# Sheet1.net
KiCad netlist of a schematic drawn in Altium Designer
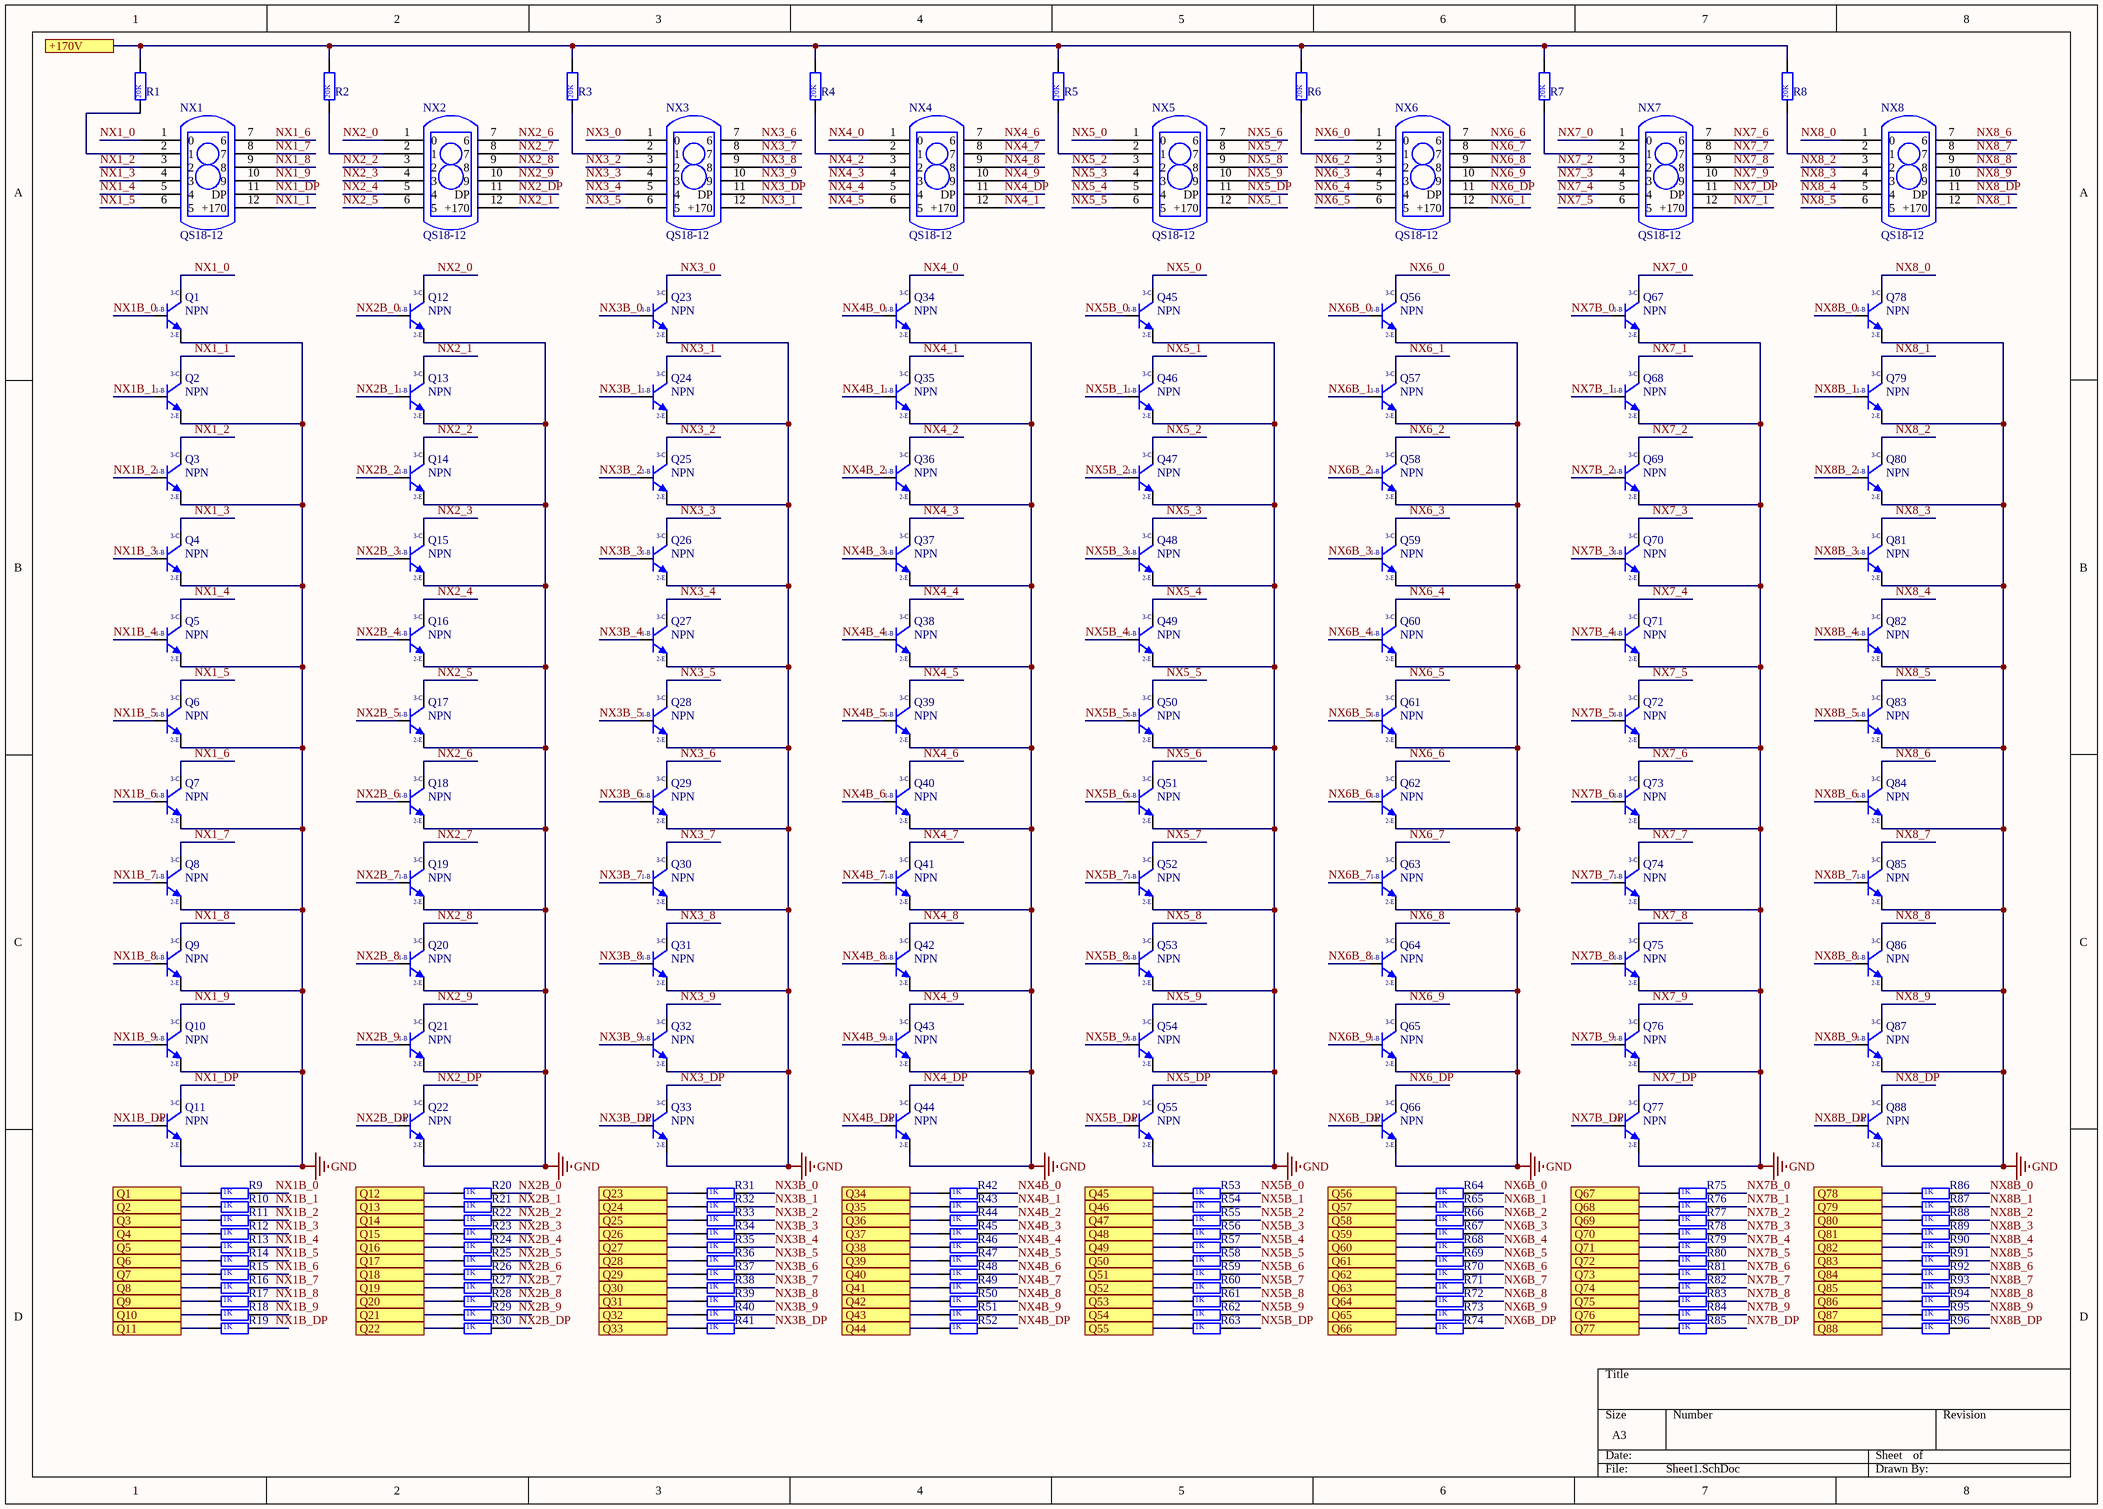
[diagram p0: Sheet1.SchDoc]

(export (version "E")
  (design (tool "Eeschema 10.0.6"))
  (components
    (comp (ref "NX1")
      (value "QS18-12")
      (footprint "PCBComponent_1")
      (libsource (lib "Nixie") (part "QS18-12"))
    )
    (comp (ref "NX2")
      (value "QS18-12")
      (footprint "PCBComponent_1")
      (libsource (lib "Nixie") (part "QS18-12"))
    )
    (comp (ref "NX3")
      (value "QS18-12")
      (footprint "PCBComponent_1")
      (libsource (lib "Nixie") (part "QS18-12"))
    )
    (comp (ref "NX4")
      (value "QS18-12")
      (footprint "PCBComponent_1")
      (libsource (lib "Nixie") (part "QS18-12"))
    )
    (comp (ref "NX5")
      (value "QS18-12")
      (footprint "PCBComponent_1")
      (libsource (lib "Nixie") (part "QS18-12"))
    )
    (comp (ref "NX6")
      (value "QS18-12")
      (footprint "PCBComponent_1")
      (libsource (lib "Nixie") (part "QS18-12"))
    )
    (comp (ref "NX7")
      (value "QS18-12")
      (footprint "PCBComponent_1")
      (libsource (lib "Nixie") (part "QS18-12"))
    )
    (comp (ref "NX8")
      (value "QS18-12")
      (footprint "PCBComponent_1")
      (libsource (lib "Nixie") (part "QS18-12"))
    )
    (comp (ref "Q1") (value "NPN") (footprint "SOT-23") (libsource (lib "吴原理图库") (part "NPN-S8050-SOT-23")))
    (comp (ref "Q2") (value "NPN") (footprint "SOT-23") (libsource (lib "吴原理图库") (part "NPN-S8050-SOT-23")))
    (comp (ref "Q3") (value "NPN") (footprint "SOT-23") (libsource (lib "吴原理图库") (part "NPN-S8050-SOT-23")))
    (comp (ref "Q4") (value "NPN") (footprint "SOT-23") (libsource (lib "吴原理图库") (part "NPN-S8050-SOT-23")))
    (comp (ref "Q5") (value "NPN") (footprint "SOT-23") (libsource (lib "吴原理图库") (part "NPN-S8050-SOT-23")))
    (comp (ref "Q6") (value "NPN") (footprint "SOT-23") (libsource (lib "吴原理图库") (part "NPN-S8050-SOT-23")))
    (comp (ref "Q7") (value "NPN") (footprint "SOT-23") (libsource (lib "吴原理图库") (part "NPN-S8050-SOT-23")))
    (comp (ref "Q8") (value "NPN") (footprint "SOT-23") (libsource (lib "吴原理图库") (part "NPN-S8050-SOT-23")))
    (comp (ref "Q9") (value "NPN") (footprint "SOT-23") (libsource (lib "吴原理图库") (part "NPN-S8050-SOT-23")))
    (comp (ref "Q10") (value "NPN") (footprint "SOT-23") (libsource (lib "吴原理图库") (part "NPN-S8050-SOT-23")))
    (comp (ref "Q11") (value "NPN") (footprint "SOT-23") (libsource (lib "吴原理图库") (part "NPN-S8050-SOT-23")))
    (comp (ref "Q12") (value "NPN") (footprint "SOT-23") (libsource (lib "吴原理图库") (part "NPN-S8050-SOT-23")))
    (comp (ref "Q13") (value "NPN") (footprint "SOT-23") (libsource (lib "吴原理图库") (part "NPN-S8050-SOT-23")))
    (comp (ref "Q14") (value "NPN") (footprint "SOT-23") (libsource (lib "吴原理图库") (part "NPN-S8050-SOT-23")))
    (comp (ref "Q15") (value "NPN") (footprint "SOT-23") (libsource (lib "吴原理图库") (part "NPN-S8050-SOT-23")))
    (comp (ref "Q16") (value "NPN") (footprint "SOT-23") (libsource (lib "吴原理图库") (part "NPN-S8050-SOT-23")))
    (comp (ref "Q17") (value "NPN") (footprint "SOT-23") (libsource (lib "吴原理图库") (part "NPN-S8050-SOT-23")))
    (comp (ref "Q18") (value "NPN") (footprint "SOT-23") (libsource (lib "吴原理图库") (part "NPN-S8050-SOT-23")))
    (comp (ref "Q19") (value "NPN") (footprint "SOT-23") (libsource (lib "吴原理图库") (part "NPN-S8050-SOT-23")))
    (comp (ref "Q20") (value "NPN") (footprint "SOT-23") (libsource (lib "吴原理图库") (part "NPN-S8050-SOT-23")))
    (comp (ref "Q21") (value "NPN") (footprint "SOT-23") (libsource (lib "吴原理图库") (part "NPN-S8050-SOT-23")))
    (comp (ref "Q22") (value "NPN") (footprint "SOT-23") (libsource (lib "吴原理图库") (part "NPN-S8050-SOT-23")))
    (comp (ref "Q23") (value "NPN") (footprint "SOT-23") (libsource (lib "吴原理图库") (part "NPN-S8050-SOT-23")))
    (comp (ref "Q24") (value "NPN") (footprint "SOT-23") (libsource (lib "吴原理图库") (part "NPN-S8050-SOT-23")))
    (comp (ref "Q25") (value "NPN") (footprint "SOT-23") (libsource (lib "吴原理图库") (part "NPN-S8050-SOT-23")))
    (comp (ref "Q26") (value "NPN") (footprint "SOT-23") (libsource (lib "吴原理图库") (part "NPN-S8050-SOT-23")))
    (comp (ref "Q27") (value "NPN") (footprint "SOT-23") (libsource (lib "吴原理图库") (part "NPN-S8050-SOT-23")))
    (comp (ref "Q28") (value "NPN") (footprint "SOT-23") (libsource (lib "吴原理图库") (part "NPN-S8050-SOT-23")))
    (comp (ref "Q29") (value "NPN") (footprint "SOT-23") (libsource (lib "吴原理图库") (part "NPN-S8050-SOT-23")))
    (comp (ref "Q30") (value "NPN") (footprint "SOT-23") (libsource (lib "吴原理图库") (part "NPN-S8050-SOT-23")))
    (comp (ref "Q31") (value "NPN") (footprint "SOT-23") (libsource (lib "吴原理图库") (part "NPN-S8050-SOT-23")))
    (comp (ref "Q32") (value "NPN") (footprint "SOT-23") (libsource (lib "吴原理图库") (part "NPN-S8050-SOT-23")))
    (comp (ref "Q33") (value "NPN") (footprint "SOT-23") (libsource (lib "吴原理图库") (part "NPN-S8050-SOT-23")))
    (comp (ref "Q34") (value "NPN") (footprint "SOT-23") (libsource (lib "吴原理图库") (part "NPN-S8050-SOT-23")))
    (comp (ref "Q35") (value "NPN") (footprint "SOT-23") (libsource (lib "吴原理图库") (part "NPN-S8050-SOT-23")))
    (comp (ref "Q36") (value "NPN") (footprint "SOT-23") (libsource (lib "吴原理图库") (part "NPN-S8050-SOT-23")))
    (comp (ref "Q37") (value "NPN") (footprint "SOT-23") (libsource (lib "吴原理图库") (part "NPN-S8050-SOT-23")))
    (comp (ref "Q38") (value "NPN") (footprint "SOT-23") (libsource (lib "吴原理图库") (part "NPN-S8050-SOT-23")))
    (comp (ref "Q39") (value "NPN") (footprint "SOT-23") (libsource (lib "吴原理图库") (part "NPN-S8050-SOT-23")))
    (comp (ref "Q40") (value "NPN") (footprint "SOT-23") (libsource (lib "吴原理图库") (part "NPN-S8050-SOT-23")))
    (comp (ref "Q41") (value "NPN") (footprint "SOT-23") (libsource (lib "吴原理图库") (part "NPN-S8050-SOT-23")))
    (comp (ref "Q42") (value "NPN") (footprint "SOT-23") (libsource (lib "吴原理图库") (part "NPN-S8050-SOT-23")))
    (comp (ref "Q43") (value "NPN") (footprint "SOT-23") (libsource (lib "吴原理图库") (part "NPN-S8050-SOT-23")))
    (comp (ref "Q44") (value "NPN") (footprint "SOT-23") (libsource (lib "吴原理图库") (part "NPN-S8050-SOT-23")))
    (comp (ref "Q45") (value "NPN") (footprint "SOT-23") (libsource (lib "吴原理图库") (part "NPN-S8050-SOT-23")))
    (comp (ref "Q46") (value "NPN") (footprint "SOT-23") (libsource (lib "吴原理图库") (part "NPN-S8050-SOT-23")))
    (comp (ref "Q47") (value "NPN") (footprint "SOT-23") (libsource (lib "吴原理图库") (part "NPN-S8050-SOT-23")))
    (comp (ref "Q48") (value "NPN") (footprint "SOT-23") (libsource (lib "吴原理图库") (part "NPN-S8050-SOT-23")))
    (comp (ref "Q49") (value "NPN") (footprint "SOT-23") (libsource (lib "吴原理图库") (part "NPN-S8050-SOT-23")))
    (comp (ref "Q50") (value "NPN") (footprint "SOT-23") (libsource (lib "吴原理图库") (part "NPN-S8050-SOT-23")))
    (comp (ref "Q51") (value "NPN") (footprint "SOT-23") (libsource (lib "吴原理图库") (part "NPN-S8050-SOT-23")))
    (comp (ref "Q52") (value "NPN") (footprint "SOT-23") (libsource (lib "吴原理图库") (part "NPN-S8050-SOT-23")))
    (comp (ref "Q53") (value "NPN") (footprint "SOT-23") (libsource (lib "吴原理图库") (part "NPN-S8050-SOT-23")))
    (comp (ref "Q54") (value "NPN") (footprint "SOT-23") (libsource (lib "吴原理图库") (part "NPN-S8050-SOT-23")))
    (comp (ref "Q55") (value "NPN") (footprint "SOT-23") (libsource (lib "吴原理图库") (part "NPN-S8050-SOT-23")))
    (comp (ref "Q56") (value "NPN") (footprint "SOT-23") (libsource (lib "吴原理图库") (part "NPN-S8050-SOT-23")))
    (comp (ref "Q57") (value "NPN") (footprint "SOT-23") (libsource (lib "吴原理图库") (part "NPN-S8050-SOT-23")))
    (comp (ref "Q58") (value "NPN") (footprint "SOT-23") (libsource (lib "吴原理图库") (part "NPN-S8050-SOT-23")))
    (comp (ref "Q59") (value "NPN") (footprint "SOT-23") (libsource (lib "吴原理图库") (part "NPN-S8050-SOT-23")))
    (comp (ref "Q60") (value "NPN") (footprint "SOT-23") (libsource (lib "吴原理图库") (part "NPN-S8050-SOT-23")))
    (comp (ref "Q61") (value "NPN") (footprint "SOT-23") (libsource (lib "吴原理图库") (part "NPN-S8050-SOT-23")))
    (comp (ref "Q62") (value "NPN") (footprint "SOT-23") (libsource (lib "吴原理图库") (part "NPN-S8050-SOT-23")))
    (comp (ref "Q63") (value "NPN") (footprint "SOT-23") (libsource (lib "吴原理图库") (part "NPN-S8050-SOT-23")))
    (comp (ref "Q64") (value "NPN") (footprint "SOT-23") (libsource (lib "吴原理图库") (part "NPN-S8050-SOT-23")))
    (comp (ref "Q65") (value "NPN") (footprint "SOT-23") (libsource (lib "吴原理图库") (part "NPN-S8050-SOT-23")))
    (comp (ref "Q66") (value "NPN") (footprint "SOT-23") (libsource (lib "吴原理图库") (part "NPN-S8050-SOT-23")))
    (comp (ref "Q67") (value "NPN") (footprint "SOT-23") (libsource (lib "吴原理图库") (part "NPN-S8050-SOT-23")))
    (comp (ref "Q68") (value "NPN") (footprint "SOT-23") (libsource (lib "吴原理图库") (part "NPN-S8050-SOT-23")))
    (comp (ref "Q69") (value "NPN") (footprint "SOT-23") (libsource (lib "吴原理图库") (part "NPN-S8050-SOT-23")))
    (comp (ref "Q70") (value "NPN") (footprint "SOT-23") (libsource (lib "吴原理图库") (part "NPN-S8050-SOT-23")))
    (comp (ref "Q71") (value "NPN") (footprint "SOT-23") (libsource (lib "吴原理图库") (part "NPN-S8050-SOT-23")))
    (comp (ref "Q72") (value "NPN") (footprint "SOT-23") (libsource (lib "吴原理图库") (part "NPN-S8050-SOT-23")))
    (comp (ref "Q73") (value "NPN") (footprint "SOT-23") (libsource (lib "吴原理图库") (part "NPN-S8050-SOT-23")))
    (comp (ref "Q74") (value "NPN") (footprint "SOT-23") (libsource (lib "吴原理图库") (part "NPN-S8050-SOT-23")))
    (comp (ref "Q75") (value "NPN") (footprint "SOT-23") (libsource (lib "吴原理图库") (part "NPN-S8050-SOT-23")))
    (comp (ref "Q76") (value "NPN") (footprint "SOT-23") (libsource (lib "吴原理图库") (part "NPN-S8050-SOT-23")))
    (comp (ref "Q77") (value "NPN") (footprint "SOT-23") (libsource (lib "吴原理图库") (part "NPN-S8050-SOT-23")))
    (comp (ref "Q78") (value "NPN") (footprint "SOT-23") (libsource (lib "吴原理图库") (part "NPN-S8050-SOT-23")))
    (comp (ref "Q79") (value "NPN") (footprint "SOT-23") (libsource (lib "吴原理图库") (part "NPN-S8050-SOT-23")))
    (comp (ref "Q80") (value "NPN") (footprint "SOT-23") (libsource (lib "吴原理图库") (part "NPN-S8050-SOT-23")))
    (comp (ref "Q81") (value "NPN") (footprint "SOT-23") (libsource (lib "吴原理图库") (part "NPN-S8050-SOT-23")))
    (comp (ref "Q82") (value "NPN") (footprint "SOT-23") (libsource (lib "吴原理图库") (part "NPN-S8050-SOT-23")))
    (comp (ref "Q83") (value "NPN") (footprint "SOT-23") (libsource (lib "吴原理图库") (part "NPN-S8050-SOT-23")))
    (comp (ref "Q84") (value "NPN") (footprint "SOT-23") (libsource (lib "吴原理图库") (part "NPN-S8050-SOT-23")))
    (comp (ref "Q85") (value "NPN") (footprint "SOT-23") (libsource (lib "吴原理图库") (part "NPN-S8050-SOT-23")))
    (comp (ref "Q86") (value "NPN") (footprint "SOT-23") (libsource (lib "吴原理图库") (part "NPN-S8050-SOT-23")))
    (comp (ref "Q87") (value "NPN") (footprint "SOT-23") (libsource (lib "吴原理图库") (part "NPN-S8050-SOT-23")))
    (comp (ref "Q88") (value "NPN") (footprint "SOT-23") (libsource (lib "吴原理图库") (part "NPN-S8050-SOT-23")))
    (comp (ref "R1")
      (value "20K")
      (footprint "0805")
      (fields (field (name "Comment") "R"))
      (libsource (lib "") (part "R_1"))
    )
    (comp (ref "R2")
      (value "20K")
      (footprint "0805")
      (fields (field (name "Comment") "R"))
      (libsource (lib "") (part "R_1"))
    )
    (comp (ref "R3")
      (value "20K")
      (footprint "0805")
      (fields (field (name "Comment") "R"))
      (libsource (lib "") (part "R_1"))
    )
    (comp (ref "R4")
      (value "20K")
      (footprint "0805")
      (fields (field (name "Comment") "R"))
      (libsource (lib "") (part "R_1"))
    )
    (comp (ref "R5")
      (value "20K")
      (footprint "0805")
      (fields (field (name "Comment") "R"))
      (libsource (lib "") (part "R_1"))
    )
    (comp (ref "R6")
      (value "20K")
      (footprint "0805")
      (fields (field (name "Comment") "R"))
      (libsource (lib "") (part "R_1"))
    )
    (comp (ref "R7")
      (value "20K")
      (footprint "0805")
      (fields (field (name "Comment") "R"))
      (libsource (lib "") (part "R_1"))
    )
    (comp (ref "R8")
      (value "20K")
      (footprint "0805")
      (fields (field (name "Comment") "R"))
      (libsource (lib "") (part "R_1"))
    )
    (comp (ref "R9")
      (value "1K")
      (footprint "0805")
      (fields (field (name "Comment") "R"))
      (libsource (lib "吴原理图库") (part "R"))
    )
    (comp (ref "R10")
      (value "1K")
      (footprint "0805")
      (fields (field (name "Comment") "R"))
      (libsource (lib "吴原理图库") (part "R"))
    )
    (comp (ref "R11")
      (value "1K")
      (footprint "0805")
      (fields (field (name "Comment") "R"))
      (libsource (lib "吴原理图库") (part "R"))
    )
    (comp (ref "R12")
      (value "1K")
      (footprint "0805")
      (fields (field (name "Comment") "R"))
      (libsource (lib "吴原理图库") (part "R"))
    )
    (comp (ref "R13")
      (value "1K")
      (footprint "0805")
      (fields (field (name "Comment") "R"))
      (libsource (lib "吴原理图库") (part "R"))
    )
    (comp (ref "R14")
      (value "1K")
      (footprint "0805")
      (fields (field (name "Comment") "R"))
      (libsource (lib "吴原理图库") (part "R"))
    )
    (comp (ref "R15")
      (value "1K")
      (footprint "0805")
      (fields (field (name "Comment") "R"))
      (libsource (lib "吴原理图库") (part "R"))
    )
    (comp (ref "R16")
      (value "1K")
      (footprint "0805")
      (fields (field (name "Comment") "R"))
      (libsource (lib "吴原理图库") (part "R"))
    )
    (comp (ref "R17")
      (value "1K")
      (footprint "0805")
      (fields (field (name "Comment") "R"))
      (libsource (lib "吴原理图库") (part "R"))
    )
    (comp (ref "R18")
      (value "1K")
      (footprint "0805")
      (fields (field (name "Comment") "R"))
      (libsource (lib "吴原理图库") (part "R"))
    )
    (comp (ref "R19")
      (value "1K")
      (footprint "0805")
      (fields (field (name "Comment") "R"))
      (libsource (lib "吴原理图库") (part "R"))
    )
    (comp (ref "R20")
      (value "1K")
      (footprint "0805")
      (fields (field (name "Comment") "R"))
      (libsource (lib "吴原理图库") (part "R"))
    )
    (comp (ref "R21")
      (value "1K")
      (footprint "0805")
      (fields (field (name "Comment") "R"))
      (libsource (lib "吴原理图库") (part "R"))
    )
    (comp (ref "R22")
      (value "1K")
      (footprint "0805")
      (fields (field (name "Comment") "R"))
      (libsource (lib "吴原理图库") (part "R"))
    )
    (comp (ref "R23")
      (value "1K")
      (footprint "0805")
      (fields (field (name "Comment") "R"))
      (libsource (lib "吴原理图库") (part "R"))
    )
    (comp (ref "R24")
      (value "1K")
      (footprint "0805")
      (fields (field (name "Comment") "R"))
      (libsource (lib "吴原理图库") (part "R"))
    )
    (comp (ref "R25")
      (value "1K")
      (footprint "0805")
      (fields (field (name "Comment") "R"))
      (libsource (lib "吴原理图库") (part "R"))
    )
    (comp (ref "R26")
      (value "1K")
      (footprint "0805")
      (fields (field (name "Comment") "R"))
      (libsource (lib "吴原理图库") (part "R"))
    )
    (comp (ref "R27")
      (value "1K")
      (footprint "0805")
      (fields (field (name "Comment") "R"))
      (libsource (lib "吴原理图库") (part "R"))
    )
    (comp (ref "R28")
      (value "1K")
      (footprint "0805")
      (fields (field (name "Comment") "R"))
      (libsource (lib "吴原理图库") (part "R"))
    )
    (comp (ref "R29")
      (value "1K")
      (footprint "0805")
      (fields (field (name "Comment") "R"))
      (libsource (lib "吴原理图库") (part "R"))
    )
    (comp (ref "R30")
      (value "1K")
      (footprint "0805")
      (fields (field (name "Comment") "R"))
      (libsource (lib "吴原理图库") (part "R"))
    )
    (comp (ref "R31")
      (value "1K")
      (footprint "0805")
      (fields (field (name "Comment") "R"))
      (libsource (lib "吴原理图库") (part "R"))
    )
    (comp (ref "R32")
      (value "1K")
      (footprint "0805")
      (fields (field (name "Comment") "R"))
      (libsource (lib "吴原理图库") (part "R"))
    )
    (comp (ref "R33")
      (value "1K")
      (footprint "0805")
      (fields (field (name "Comment") "R"))
      (libsource (lib "吴原理图库") (part "R"))
    )
    (comp (ref "R34")
      (value "1K")
      (footprint "0805")
      (fields (field (name "Comment") "R"))
      (libsource (lib "吴原理图库") (part "R"))
    )
    (comp (ref "R35")
      (value "1K")
      (footprint "0805")
      (fields (field (name "Comment") "R"))
      (libsource (lib "吴原理图库") (part "R"))
    )
    (comp (ref "R36")
      (value "1K")
      (footprint "0805")
      (fields (field (name "Comment") "R"))
      (libsource (lib "吴原理图库") (part "R"))
    )
    (comp (ref "R37")
      (value "1K")
      (footprint "0805")
      (fields (field (name "Comment") "R"))
      (libsource (lib "吴原理图库") (part "R"))
    )
    (comp (ref "R38")
      (value "1K")
      (footprint "0805")
      (fields (field (name "Comment") "R"))
      (libsource (lib "吴原理图库") (part "R"))
    )
    (comp (ref "R39")
      (value "1K")
      (footprint "0805")
      (fields (field (name "Comment") "R"))
      (libsource (lib "吴原理图库") (part "R"))
    )
    (comp (ref "R40")
      (value "1K")
      (footprint "0805")
      (fields (field (name "Comment") "R"))
      (libsource (lib "吴原理图库") (part "R"))
    )
    (comp (ref "R41")
      (value "1K")
      (footprint "0805")
      (fields (field (name "Comment") "R"))
      (libsource (lib "吴原理图库") (part "R"))
    )
    (comp (ref "R42")
      (value "1K")
      (footprint "0805")
      (fields (field (name "Comment") "R"))
      (libsource (lib "吴原理图库") (part "R"))
    )
    (comp (ref "R43")
      (value "1K")
      (footprint "0805")
      (fields (field (name "Comment") "R"))
      (libsource (lib "吴原理图库") (part "R"))
    )
    (comp (ref "R44")
      (value "1K")
      (footprint "0805")
      (fields (field (name "Comment") "R"))
      (libsource (lib "吴原理图库") (part "R"))
    )
    (comp (ref "R45")
      (value "1K")
      (footprint "0805")
      (fields (field (name "Comment") "R"))
      (libsource (lib "吴原理图库") (part "R"))
    )
    (comp (ref "R46")
      (value "1K")
      (footprint "0805")
      (fields (field (name "Comment") "R"))
      (libsource (lib "吴原理图库") (part "R"))
    )
    (comp (ref "R47")
      (value "1K")
      (footprint "0805")
      (fields (field (name "Comment") "R"))
      (libsource (lib "吴原理图库") (part "R"))
    )
    (comp (ref "R48")
      (value "1K")
      (footprint "0805")
      (fields (field (name "Comment") "R"))
      (libsource (lib "吴原理图库") (part "R"))
    )
    (comp (ref "R49")
      (value "1K")
      (footprint "0805")
      (fields (field (name "Comment") "R"))
      (libsource (lib "吴原理图库") (part "R"))
    )
    (comp (ref "R50")
      (value "1K")
      (footprint "0805")
      (fields (field (name "Comment") "R"))
      (libsource (lib "吴原理图库") (part "R"))
    )
    (comp (ref "R51")
      (value "1K")
      (footprint "0805")
      (fields (field (name "Comment") "R"))
      (libsource (lib "吴原理图库") (part "R"))
    )
    (comp (ref "R52")
      (value "1K")
      (footprint "0805")
      (fields (field (name "Comment") "R"))
      (libsource (lib "吴原理图库") (part "R"))
    )
    (comp (ref "R53")
      (value "1K")
      (footprint "0805")
      (fields (field (name "Comment") "R"))
      (libsource (lib "吴原理图库") (part "R"))
    )
    (comp (ref "R54")
      (value "1K")
      (footprint "0805")
      (fields (field (name "Comment") "R"))
      (libsource (lib "吴原理图库") (part "R"))
    )
    (comp (ref "R55")
      (value "1K")
      (footprint "0805")
      (fields (field (name "Comment") "R"))
      (libsource (lib "吴原理图库") (part "R"))
    )
    (comp (ref "R56")
      (value "1K")
      (footprint "0805")
      (fields (field (name "Comment") "R"))
      (libsource (lib "吴原理图库") (part "R"))
    )
    (comp (ref "R57")
      (value "1K")
      (footprint "0805")
      (fields (field (name "Comment") "R"))
      (libsource (lib "吴原理图库") (part "R"))
    )
    (comp (ref "R58")
      (value "1K")
      (footprint "0805")
      (fields (field (name "Comment") "R"))
      (libsource (lib "吴原理图库") (part "R"))
    )
    (comp (ref "R59")
      (value "1K")
      (footprint "0805")
      (fields (field (name "Comment") "R"))
      (libsource (lib "吴原理图库") (part "R"))
    )
    (comp (ref "R60")
      (value "1K")
      (footprint "0805")
      (fields (field (name "Comment") "R"))
      (libsource (lib "吴原理图库") (part "R"))
    )
    (comp (ref "R61")
      (value "1K")
      (footprint "0805")
      (fields (field (name "Comment") "R"))
      (libsource (lib "吴原理图库") (part "R"))
    )
    (comp (ref "R62")
      (value "1K")
      (footprint "0805")
      (fields (field (name "Comment") "R"))
      (libsource (lib "吴原理图库") (part "R"))
    )
    (comp (ref "R63")
      (value "1K")
      (footprint "0805")
      (fields (field (name "Comment") "R"))
      (libsource (lib "吴原理图库") (part "R"))
    )
    (comp (ref "R64")
      (value "1K")
      (footprint "0805")
      (fields (field (name "Comment") "R"))
      (libsource (lib "吴原理图库") (part "R"))
    )
    (comp (ref "R65")
      (value "1K")
      (footprint "0805")
      (fields (field (name "Comment") "R"))
      (libsource (lib "吴原理图库") (part "R"))
    )
    (comp (ref "R66")
      (value "1K")
      (footprint "0805")
      (fields (field (name "Comment") "R"))
      (libsource (lib "吴原理图库") (part "R"))
    )
    (comp (ref "R67")
      (value "1K")
      (footprint "0805")
      (fields (field (name "Comment") "R"))
      (libsource (lib "吴原理图库") (part "R"))
    )
    (comp (ref "R68")
      (value "1K")
      (footprint "0805")
      (fields (field (name "Comment") "R"))
      (libsource (lib "吴原理图库") (part "R"))
    )
    (comp (ref "R69")
      (value "1K")
      (footprint "0805")
      (fields (field (name "Comment") "R"))
      (libsource (lib "吴原理图库") (part "R"))
    )
    (comp (ref "R70")
      (value "1K")
      (footprint "0805")
      (fields (field (name "Comment") "R"))
      (libsource (lib "吴原理图库") (part "R"))
    )
    (comp (ref "R71")
      (value "1K")
      (footprint "0805")
      (fields (field (name "Comment") "R"))
      (libsource (lib "吴原理图库") (part "R"))
    )
    (comp (ref "R72")
      (value "1K")
      (footprint "0805")
      (fields (field (name "Comment") "R"))
      (libsource (lib "吴原理图库") (part "R"))
    )
    (comp (ref "R73")
      (value "1K")
      (footprint "0805")
      (fields (field (name "Comment") "R"))
      (libsource (lib "吴原理图库") (part "R"))
    )
    (comp (ref "R74")
      (value "1K")
      (footprint "0805")
      (fields (field (name "Comment") "R"))
      (libsource (lib "吴原理图库") (part "R"))
    )
    (comp (ref "R75")
      (value "1K")
      (footprint "0805")
      (fields (field (name "Comment") "R"))
      (libsource (lib "吴原理图库") (part "R"))
    )
    (comp (ref "R76")
      (value "1K")
      (footprint "0805")
      (fields (field (name "Comment") "R"))
      (libsource (lib "吴原理图库") (part "R"))
    )
    (comp (ref "R77")
      (value "1K")
      (footprint "0805")
      (fields (field (name "Comment") "R"))
      (libsource (lib "吴原理图库") (part "R"))
    )
    (comp (ref "R78")
      (value "1K")
      (footprint "0805")
      (fields (field (name "Comment") "R"))
      (libsource (lib "吴原理图库") (part "R"))
    )
    (comp (ref "R79")
      (value "1K")
      (footprint "0805")
      (fields (field (name "Comment") "R"))
      (libsource (lib "吴原理图库") (part "R"))
    )
    (comp (ref "R80")
      (value "1K")
      (footprint "0805")
      (fields (field (name "Comment") "R"))
      (libsource (lib "吴原理图库") (part "R"))
    )
    (comp (ref "R81")
      (value "1K")
      (footprint "0805")
      (fields (field (name "Comment") "R"))
      (libsource (lib "吴原理图库") (part "R"))
    )
    (comp (ref "R82")
      (value "1K")
      (footprint "0805")
      (fields (field (name "Comment") "R"))
      (libsource (lib "吴原理图库") (part "R"))
    )
    (comp (ref "R83")
      (value "1K")
      (footprint "0805")
      (fields (field (name "Comment") "R"))
      (libsource (lib "吴原理图库") (part "R"))
    )
    (comp (ref "R84")
      (value "1K")
      (footprint "0805")
      (fields (field (name "Comment") "R"))
      (libsource (lib "吴原理图库") (part "R"))
    )
    (comp (ref "R85")
      (value "1K")
      (footprint "0805")
      (fields (field (name "Comment") "R"))
      (libsource (lib "吴原理图库") (part "R"))
    )
    (comp (ref "R86")
      (value "1K")
      (footprint "0805")
      (fields (field (name "Comment") "R"))
      (libsource (lib "吴原理图库") (part "R"))
    )
    (comp (ref "R87")
      (value "1K")
      (footprint "0805")
      (fields (field (name "Comment") "R"))
      (libsource (lib "吴原理图库") (part "R"))
    )
    (comp (ref "R88")
      (value "1K")
      (footprint "0805")
      (fields (field (name "Comment") "R"))
      (libsource (lib "吴原理图库") (part "R"))
    )
    (comp (ref "R89")
      (value "1K")
      (footprint "0805")
      (fields (field (name "Comment") "R"))
      (libsource (lib "吴原理图库") (part "R"))
    )
    (comp (ref "R90")
      (value "1K")
      (footprint "0805")
      (fields (field (name "Comment") "R"))
      (libsource (lib "吴原理图库") (part "R"))
    )
    (comp (ref "R91")
      (value "1K")
      (footprint "0805")
      (fields (field (name "Comment") "R"))
      (libsource (lib "吴原理图库") (part "R"))
    )
    (comp (ref "R92")
      (value "1K")
      (footprint "0805")
      (fields (field (name "Comment") "R"))
      (libsource (lib "吴原理图库") (part "R"))
    )
    (comp (ref "R93")
      (value "1K")
      (footprint "0805")
      (fields (field (name "Comment") "R"))
      (libsource (lib "吴原理图库") (part "R"))
    )
    (comp (ref "R94")
      (value "1K")
      (footprint "0805")
      (fields (field (name "Comment") "R"))
      (libsource (lib "吴原理图库") (part "R"))
    )
    (comp (ref "R95")
      (value "1K")
      (footprint "0805")
      (fields (field (name "Comment") "R"))
      (libsource (lib "吴原理图库") (part "R"))
    )
    (comp (ref "R96")
      (value "1K")
      (footprint "0805")
      (fields (field (name "Comment") "R"))
      (libsource (lib "吴原理图库") (part "R"))
    )
  )
  (nets
    (net (code "1") (name "/+170V") (class "Default")
      (node (ref "R1") (pin "2") (pinfunction "2_2") (pintype "passive"))
      (node (ref "R2") (pin "2") (pinfunction "2_2") (pintype "passive"))
      (node (ref "R3") (pin "2") (pinfunction "2_2") (pintype "passive"))
      (node (ref "R4") (pin "2") (pinfunction "2_2") (pintype "passive"))
      (node (ref "R5") (pin "2") (pinfunction "2_2") (pintype "passive"))
      (node (ref "R6") (pin "2") (pinfunction "2_2") (pintype "passive"))
      (node (ref "R7") (pin "2") (pinfunction "2_2") (pintype "passive"))
      (node (ref "R8") (pin "2") (pinfunction "2_2") (pintype "passive"))
    )
    (net (code "2") (name "/NX1B_0") (class "Default")
      (node (ref "Q1") (pin "1") (pinfunction "B_1") (pintype "passive"))
      (node (ref "R9") (pin "2") (pinfunction "2_2") (pintype "passive"))
    )
    (net (code "3") (name "/NX1B_1") (class "Default")
      (node (ref "Q2") (pin "1") (pinfunction "B_1") (pintype "passive"))
      (node (ref "R10") (pin "2") (pinfunction "2_2") (pintype "passive"))
    )
    (net (code "4") (name "/NX1B_2") (class "Default")
      (node (ref "Q3") (pin "1") (pinfunction "B_1") (pintype "passive"))
      (node (ref "R11") (pin "2") (pinfunction "2_2") (pintype "passive"))
    )
    (net (code "5") (name "/NX1B_3") (class "Default")
      (node (ref "Q4") (pin "1") (pinfunction "B_1") (pintype "passive"))
      (node (ref "R12") (pin "2") (pinfunction "2_2") (pintype "passive"))
    )
    (net (code "6") (name "/NX1B_4") (class "Default")
      (node (ref "Q5") (pin "1") (pinfunction "B_1") (pintype "passive"))
      (node (ref "R13") (pin "2") (pinfunction "2_2") (pintype "passive"))
    )
    (net (code "7") (name "/NX1B_5") (class "Default")
      (node (ref "Q6") (pin "1") (pinfunction "B_1") (pintype "passive"))
      (node (ref "R14") (pin "2") (pinfunction "2_2") (pintype "passive"))
    )
    (net (code "8") (name "/NX1B_6") (class "Default")
      (node (ref "Q7") (pin "1") (pinfunction "B_1") (pintype "passive"))
      (node (ref "R15") (pin "2") (pinfunction "2_2") (pintype "passive"))
    )
    (net (code "9") (name "/NX1B_7") (class "Default")
      (node (ref "Q8") (pin "1") (pinfunction "B_1") (pintype "passive"))
      (node (ref "R16") (pin "2") (pinfunction "2_2") (pintype "passive"))
    )
    (net (code "10") (name "/NX1B_8") (class "Default")
      (node (ref "Q9") (pin "1") (pinfunction "B_1") (pintype "passive"))
      (node (ref "R17") (pin "2") (pinfunction "2_2") (pintype "passive"))
    )
    (net (code "11") (name "/NX1B_9") (class "Default")
      (node (ref "Q10") (pin "1") (pinfunction "B_1") (pintype "passive"))
      (node (ref "R18") (pin "2") (pinfunction "2_2") (pintype "passive"))
    )
    (net (code "12") (name "/NX1B_DP") (class "Default")
      (node (ref "Q11") (pin "1") (pinfunction "B_1") (pintype "passive"))
      (node (ref "R19") (pin "2") (pinfunction "2_2") (pintype "passive"))
    )
    (net (code "13") (name "/NX1_0") (class "Default")
      (node (ref "NX1") (pin "1") (pinfunction "0_1") (pintype "passive"))
      (node (ref "Q1") (pin "3") (pinfunction "C_3") (pintype "passive"))
    )
    (net (code "14") (name "/NX1_1") (class "Default")
      (node (ref "NX1") (pin "12") (pinfunction "+170_12") (pintype "passive"))
      (node (ref "Q2") (pin "3") (pinfunction "C_3") (pintype "passive"))
    )
    (net (code "15") (name "/NX1_2") (class "Default")
      (node (ref "NX1") (pin "3") (pinfunction "2_3") (pintype "passive"))
      (node (ref "Q3") (pin "3") (pinfunction "C_3") (pintype "passive"))
    )
    (net (code "16") (name "/NX1_3") (class "Default")
      (node (ref "NX1") (pin "4") (pinfunction "3_4") (pintype "passive"))
      (node (ref "Q4") (pin "3") (pinfunction "C_3") (pintype "passive"))
    )
    (net (code "17") (name "/NX1_4") (class "Default")
      (node (ref "NX1") (pin "5") (pinfunction "4_5") (pintype "passive"))
      (node (ref "Q5") (pin "3") (pinfunction "C_3") (pintype "passive"))
    )
    (net (code "18") (name "/NX1_5") (class "Default")
      (node (ref "NX1") (pin "6") (pinfunction "5_6") (pintype "passive"))
      (node (ref "Q6") (pin "3") (pinfunction "C_3") (pintype "passive"))
    )
    (net (code "19") (name "/NX1_6") (class "Default")
      (node (ref "NX1") (pin "7") (pinfunction "6_7") (pintype "passive"))
      (node (ref "Q7") (pin "3") (pinfunction "C_3") (pintype "passive"))
    )
    (net (code "20") (name "/NX1_7") (class "Default")
      (node (ref "NX1") (pin "8") (pinfunction "7_8") (pintype "passive"))
      (node (ref "Q8") (pin "3") (pinfunction "C_3") (pintype "passive"))
    )
    (net (code "21") (name "/NX1_8") (class "Default")
      (node (ref "NX1") (pin "9") (pinfunction "8_9") (pintype "passive"))
      (node (ref "Q9") (pin "3") (pinfunction "C_3") (pintype "passive"))
    )
    (net (code "22") (name "/NX1_9") (class "Default")
      (node (ref "NX1") (pin "10") (pinfunction "9_10") (pintype "passive"))
      (node (ref "Q10") (pin "3") (pinfunction "C_3") (pintype "passive"))
    )
    (net (code "23") (name "/NX1_DP") (class "Default")
      (node (ref "NX1") (pin "11") (pinfunction "DP_11") (pintype "passive"))
      (node (ref "Q11") (pin "3") (pinfunction "C_3") (pintype "passive"))
    )
    (net (code "24") (name "/NX2B_0") (class "Default")
      (node (ref "Q12") (pin "1") (pinfunction "B_1") (pintype "passive"))
      (node (ref "R20") (pin "2") (pinfunction "2_2") (pintype "passive"))
    )
    (net (code "25") (name "/NX2B_1") (class "Default")
      (node (ref "Q13") (pin "1") (pinfunction "B_1") (pintype "passive"))
      (node (ref "R21") (pin "2") (pinfunction "2_2") (pintype "passive"))
    )
    (net (code "26") (name "/NX2B_2") (class "Default")
      (node (ref "Q14") (pin "1") (pinfunction "B_1") (pintype "passive"))
      (node (ref "R22") (pin "2") (pinfunction "2_2") (pintype "passive"))
    )
    (net (code "27") (name "/NX2B_3") (class "Default")
      (node (ref "Q15") (pin "1") (pinfunction "B_1") (pintype "passive"))
      (node (ref "R23") (pin "2") (pinfunction "2_2") (pintype "passive"))
    )
    (net (code "28") (name "/NX2B_4") (class "Default")
      (node (ref "Q16") (pin "1") (pinfunction "B_1") (pintype "passive"))
      (node (ref "R24") (pin "2") (pinfunction "2_2") (pintype "passive"))
    )
    (net (code "29") (name "/NX2B_5") (class "Default")
      (node (ref "Q17") (pin "1") (pinfunction "B_1") (pintype "passive"))
      (node (ref "R25") (pin "2") (pinfunction "2_2") (pintype "passive"))
    )
    (net (code "30") (name "/NX2B_6") (class "Default")
      (node (ref "Q18") (pin "1") (pinfunction "B_1") (pintype "passive"))
      (node (ref "R26") (pin "2") (pinfunction "2_2") (pintype "passive"))
    )
    (net (code "31") (name "/NX2B_7") (class "Default")
      (node (ref "Q19") (pin "1") (pinfunction "B_1") (pintype "passive"))
      (node (ref "R27") (pin "2") (pinfunction "2_2") (pintype "passive"))
    )
    (net (code "32") (name "/NX2B_8") (class "Default")
      (node (ref "Q20") (pin "1") (pinfunction "B_1") (pintype "passive"))
      (node (ref "R28") (pin "2") (pinfunction "2_2") (pintype "passive"))
    )
    (net (code "33") (name "/NX2B_9") (class "Default")
      (node (ref "Q21") (pin "1") (pinfunction "B_1") (pintype "passive"))
      (node (ref "R29") (pin "2") (pinfunction "2_2") (pintype "passive"))
    )
    (net (code "34") (name "/NX2B_DP") (class "Default")
      (node (ref "Q22") (pin "1") (pinfunction "B_1") (pintype "passive"))
      (node (ref "R30") (pin "2") (pinfunction "2_2") (pintype "passive"))
    )
    (net (code "35") (name "/NX2_0") (class "Default")
      (node (ref "NX2") (pin "1") (pinfunction "0_1") (pintype "passive"))
      (node (ref "Q12") (pin "3") (pinfunction "C_3") (pintype "passive"))
    )
    (net (code "36") (name "/NX2_1") (class "Default")
      (node (ref "NX2") (pin "12") (pinfunction "+170_12") (pintype "passive"))
      (node (ref "Q13") (pin "3") (pinfunction "C_3") (pintype "passive"))
    )
    (net (code "37") (name "/NX2_2") (class "Default")
      (node (ref "NX2") (pin "3") (pinfunction "2_3") (pintype "passive"))
      (node (ref "Q14") (pin "3") (pinfunction "C_3") (pintype "passive"))
    )
    (net (code "38") (name "/NX2_3") (class "Default")
      (node (ref "NX2") (pin "4") (pinfunction "3_4") (pintype "passive"))
      (node (ref "Q15") (pin "3") (pinfunction "C_3") (pintype "passive"))
    )
    (net (code "39") (name "/NX2_4") (class "Default")
      (node (ref "NX2") (pin "5") (pinfunction "4_5") (pintype "passive"))
      (node (ref "Q16") (pin "3") (pinfunction "C_3") (pintype "passive"))
    )
    (net (code "40") (name "/NX2_5") (class "Default")
      (node (ref "NX2") (pin "6") (pinfunction "5_6") (pintype "passive"))
      (node (ref "Q17") (pin "3") (pinfunction "C_3") (pintype "passive"))
    )
    (net (code "41") (name "/NX2_6") (class "Default")
      (node (ref "NX2") (pin "7") (pinfunction "6_7") (pintype "passive"))
      (node (ref "Q18") (pin "3") (pinfunction "C_3") (pintype "passive"))
    )
    (net (code "42") (name "/NX2_7") (class "Default")
      (node (ref "NX2") (pin "8") (pinfunction "7_8") (pintype "passive"))
      (node (ref "Q19") (pin "3") (pinfunction "C_3") (pintype "passive"))
    )
    (net (code "43") (name "/NX2_8") (class "Default")
      (node (ref "NX2") (pin "9") (pinfunction "8_9") (pintype "passive"))
      (node (ref "Q20") (pin "3") (pinfunction "C_3") (pintype "passive"))
    )
    (net (code "44") (name "/NX2_9") (class "Default")
      (node (ref "NX2") (pin "10") (pinfunction "9_10") (pintype "passive"))
      (node (ref "Q21") (pin "3") (pinfunction "C_3") (pintype "passive"))
    )
    (net (code "45") (name "/NX2_DP") (class "Default")
      (node (ref "NX2") (pin "11") (pinfunction "DP_11") (pintype "passive"))
      (node (ref "Q22") (pin "3") (pinfunction "C_3") (pintype "passive"))
    )
    (net (code "46") (name "/NX3B_0") (class "Default")
      (node (ref "Q23") (pin "1") (pinfunction "B_1") (pintype "passive"))
      (node (ref "R31") (pin "2") (pinfunction "2_2") (pintype "passive"))
    )
    (net (code "47") (name "/NX3B_1") (class "Default")
      (node (ref "Q24") (pin "1") (pinfunction "B_1") (pintype "passive"))
      (node (ref "R32") (pin "2") (pinfunction "2_2") (pintype "passive"))
    )
    (net (code "48") (name "/NX3B_2") (class "Default")
      (node (ref "Q25") (pin "1") (pinfunction "B_1") (pintype "passive"))
      (node (ref "R33") (pin "2") (pinfunction "2_2") (pintype "passive"))
    )
    (net (code "49") (name "/NX3B_3") (class "Default")
      (node (ref "Q26") (pin "1") (pinfunction "B_1") (pintype "passive"))
      (node (ref "R34") (pin "2") (pinfunction "2_2") (pintype "passive"))
    )
    (net (code "50") (name "/NX3B_4") (class "Default")
      (node (ref "Q27") (pin "1") (pinfunction "B_1") (pintype "passive"))
      (node (ref "R35") (pin "2") (pinfunction "2_2") (pintype "passive"))
    )
    (net (code "51") (name "/NX3B_5") (class "Default")
      (node (ref "Q28") (pin "1") (pinfunction "B_1") (pintype "passive"))
      (node (ref "R36") (pin "2") (pinfunction "2_2") (pintype "passive"))
    )
    (net (code "52") (name "/NX3B_6") (class "Default")
      (node (ref "Q29") (pin "1") (pinfunction "B_1") (pintype "passive"))
      (node (ref "R37") (pin "2") (pinfunction "2_2") (pintype "passive"))
    )
    (net (code "53") (name "/NX3B_7") (class "Default")
      (node (ref "Q30") (pin "1") (pinfunction "B_1") (pintype "passive"))
      (node (ref "R38") (pin "2") (pinfunction "2_2") (pintype "passive"))
    )
    (net (code "54") (name "/NX3B_8") (class "Default")
      (node (ref "Q31") (pin "1") (pinfunction "B_1") (pintype "passive"))
      (node (ref "R39") (pin "2") (pinfunction "2_2") (pintype "passive"))
    )
    (net (code "55") (name "/NX3B_9") (class "Default")
      (node (ref "Q32") (pin "1") (pinfunction "B_1") (pintype "passive"))
      (node (ref "R40") (pin "2") (pinfunction "2_2") (pintype "passive"))
    )
    (net (code "56") (name "/NX3B_DP") (class "Default")
      (node (ref "Q33") (pin "1") (pinfunction "B_1") (pintype "passive"))
      (node (ref "R41") (pin "2") (pinfunction "2_2") (pintype "passive"))
    )
    (net (code "57") (name "/NX3_0") (class "Default")
      (node (ref "NX3") (pin "1") (pinfunction "0_1") (pintype "passive"))
      (node (ref "Q23") (pin "3") (pinfunction "C_3") (pintype "passive"))
    )
    (net (code "58") (name "/NX3_1") (class "Default")
      (node (ref "NX3") (pin "12") (pinfunction "+170_12") (pintype "passive"))
      (node (ref "Q24") (pin "3") (pinfunction "C_3") (pintype "passive"))
    )
    (net (code "59") (name "/NX3_2") (class "Default")
      (node (ref "NX3") (pin "3") (pinfunction "2_3") (pintype "passive"))
      (node (ref "Q25") (pin "3") (pinfunction "C_3") (pintype "passive"))
    )
    (net (code "60") (name "/NX3_3") (class "Default")
      (node (ref "NX3") (pin "4") (pinfunction "3_4") (pintype "passive"))
      (node (ref "Q26") (pin "3") (pinfunction "C_3") (pintype "passive"))
    )
    (net (code "61") (name "/NX3_4") (class "Default")
      (node (ref "NX3") (pin "5") (pinfunction "4_5") (pintype "passive"))
      (node (ref "Q27") (pin "3") (pinfunction "C_3") (pintype "passive"))
    )
    (net (code "62") (name "/NX3_5") (class "Default")
      (node (ref "NX3") (pin "6") (pinfunction "5_6") (pintype "passive"))
      (node (ref "Q28") (pin "3") (pinfunction "C_3") (pintype "passive"))
    )
    (net (code "63") (name "/NX3_6") (class "Default")
      (node (ref "NX3") (pin "7") (pinfunction "6_7") (pintype "passive"))
      (node (ref "Q29") (pin "3") (pinfunction "C_3") (pintype "passive"))
    )
    (net (code "64") (name "/NX3_7") (class "Default")
      (node (ref "NX3") (pin "8") (pinfunction "7_8") (pintype "passive"))
      (node (ref "Q30") (pin "3") (pinfunction "C_3") (pintype "passive"))
    )
    (net (code "65") (name "/NX3_8") (class "Default")
      (node (ref "NX3") (pin "9") (pinfunction "8_9") (pintype "passive"))
      (node (ref "Q31") (pin "3") (pinfunction "C_3") (pintype "passive"))
    )
    (net (code "66") (name "/NX3_9") (class "Default")
      (node (ref "NX3") (pin "10") (pinfunction "9_10") (pintype "passive"))
      (node (ref "Q32") (pin "3") (pinfunction "C_3") (pintype "passive"))
    )
    (net (code "67") (name "/NX3_DP") (class "Default")
      (node (ref "NX3") (pin "11") (pinfunction "DP_11") (pintype "passive"))
      (node (ref "Q33") (pin "3") (pinfunction "C_3") (pintype "passive"))
    )
    (net (code "68") (name "/NX4B_0") (class "Default")
      (node (ref "Q34") (pin "1") (pinfunction "B_1") (pintype "passive"))
      (node (ref "R42") (pin "2") (pinfunction "2_2") (pintype "passive"))
    )
    (net (code "69") (name "/NX4B_1") (class "Default")
      (node (ref "Q35") (pin "1") (pinfunction "B_1") (pintype "passive"))
      (node (ref "R43") (pin "2") (pinfunction "2_2") (pintype "passive"))
    )
    (net (code "70") (name "/NX4B_2") (class "Default")
      (node (ref "Q36") (pin "1") (pinfunction "B_1") (pintype "passive"))
      (node (ref "R44") (pin "2") (pinfunction "2_2") (pintype "passive"))
    )
    (net (code "71") (name "/NX4B_3") (class "Default")
      (node (ref "Q37") (pin "1") (pinfunction "B_1") (pintype "passive"))
      (node (ref "R45") (pin "2") (pinfunction "2_2") (pintype "passive"))
    )
    (net (code "72") (name "/NX4B_4") (class "Default")
      (node (ref "Q38") (pin "1") (pinfunction "B_1") (pintype "passive"))
      (node (ref "R46") (pin "2") (pinfunction "2_2") (pintype "passive"))
    )
    (net (code "73") (name "/NX4B_5") (class "Default")
      (node (ref "Q39") (pin "1") (pinfunction "B_1") (pintype "passive"))
      (node (ref "R47") (pin "2") (pinfunction "2_2") (pintype "passive"))
    )
    (net (code "74") (name "/NX4B_6") (class "Default")
      (node (ref "Q40") (pin "1") (pinfunction "B_1") (pintype "passive"))
      (node (ref "R48") (pin "2") (pinfunction "2_2") (pintype "passive"))
    )
    (net (code "75") (name "/NX4B_7") (class "Default")
      (node (ref "Q41") (pin "1") (pinfunction "B_1") (pintype "passive"))
      (node (ref "R49") (pin "2") (pinfunction "2_2") (pintype "passive"))
    )
    (net (code "76") (name "/NX4B_8") (class "Default")
      (node (ref "Q42") (pin "1") (pinfunction "B_1") (pintype "passive"))
      (node (ref "R50") (pin "2") (pinfunction "2_2") (pintype "passive"))
    )
    (net (code "77") (name "/NX4B_9") (class "Default")
      (node (ref "Q43") (pin "1") (pinfunction "B_1") (pintype "passive"))
      (node (ref "R51") (pin "2") (pinfunction "2_2") (pintype "passive"))
    )
    (net (code "78") (name "/NX4B_DP") (class "Default")
      (node (ref "Q44") (pin "1") (pinfunction "B_1") (pintype "passive"))
      (node (ref "R52") (pin "2") (pinfunction "2_2") (pintype "passive"))
    )
    (net (code "79") (name "/NX4_0") (class "Default")
      (node (ref "NX4") (pin "1") (pinfunction "0_1") (pintype "passive"))
      (node (ref "Q34") (pin "3") (pinfunction "C_3") (pintype "passive"))
    )
    (net (code "80") (name "/NX4_1") (class "Default")
      (node (ref "NX4") (pin "12") (pinfunction "+170_12") (pintype "passive"))
      (node (ref "Q35") (pin "3") (pinfunction "C_3") (pintype "passive"))
    )
    (net (code "81") (name "/NX4_2") (class "Default")
      (node (ref "NX4") (pin "3") (pinfunction "2_3") (pintype "passive"))
      (node (ref "Q36") (pin "3") (pinfunction "C_3") (pintype "passive"))
    )
    (net (code "82") (name "/NX4_3") (class "Default")
      (node (ref "NX4") (pin "4") (pinfunction "3_4") (pintype "passive"))
      (node (ref "Q37") (pin "3") (pinfunction "C_3") (pintype "passive"))
    )
    (net (code "83") (name "/NX4_4") (class "Default")
      (node (ref "NX4") (pin "5") (pinfunction "4_5") (pintype "passive"))
      (node (ref "Q38") (pin "3") (pinfunction "C_3") (pintype "passive"))
    )
    (net (code "84") (name "/NX4_5") (class "Default")
      (node (ref "NX4") (pin "6") (pinfunction "5_6") (pintype "passive"))
      (node (ref "Q39") (pin "3") (pinfunction "C_3") (pintype "passive"))
    )
    (net (code "85") (name "/NX4_6") (class "Default")
      (node (ref "NX4") (pin "7") (pinfunction "6_7") (pintype "passive"))
      (node (ref "Q40") (pin "3") (pinfunction "C_3") (pintype "passive"))
    )
    (net (code "86") (name "/NX4_7") (class "Default")
      (node (ref "NX4") (pin "8") (pinfunction "7_8") (pintype "passive"))
      (node (ref "Q41") (pin "3") (pinfunction "C_3") (pintype "passive"))
    )
    (net (code "87") (name "/NX4_8") (class "Default")
      (node (ref "NX4") (pin "9") (pinfunction "8_9") (pintype "passive"))
      (node (ref "Q42") (pin "3") (pinfunction "C_3") (pintype "passive"))
    )
    (net (code "88") (name "/NX4_9") (class "Default")
      (node (ref "NX4") (pin "10") (pinfunction "9_10") (pintype "passive"))
      (node (ref "Q43") (pin "3") (pinfunction "C_3") (pintype "passive"))
    )
    (net (code "89") (name "/NX4_DP") (class "Default")
      (node (ref "NX4") (pin "11") (pinfunction "DP_11") (pintype "passive"))
      (node (ref "Q44") (pin "3") (pinfunction "C_3") (pintype "passive"))
    )
    (net (code "90") (name "/NX5B_0") (class "Default")
      (node (ref "Q45") (pin "1") (pinfunction "B_1") (pintype "passive"))
      (node (ref "R53") (pin "2") (pinfunction "2_2") (pintype "passive"))
    )
    (net (code "91") (name "/NX5B_1") (class "Default")
      (node (ref "Q46") (pin "1") (pinfunction "B_1") (pintype "passive"))
      (node (ref "R54") (pin "2") (pinfunction "2_2") (pintype "passive"))
    )
    (net (code "92") (name "/NX5B_2") (class "Default")
      (node (ref "Q47") (pin "1") (pinfunction "B_1") (pintype "passive"))
      (node (ref "R55") (pin "2") (pinfunction "2_2") (pintype "passive"))
    )
    (net (code "93") (name "/NX5B_3") (class "Default")
      (node (ref "Q48") (pin "1") (pinfunction "B_1") (pintype "passive"))
      (node (ref "R56") (pin "2") (pinfunction "2_2") (pintype "passive"))
    )
    (net (code "94") (name "/NX5B_4") (class "Default")
      (node (ref "Q49") (pin "1") (pinfunction "B_1") (pintype "passive"))
      (node (ref "R57") (pin "2") (pinfunction "2_2") (pintype "passive"))
    )
    (net (code "95") (name "/NX5B_5") (class "Default")
      (node (ref "Q50") (pin "1") (pinfunction "B_1") (pintype "passive"))
      (node (ref "R58") (pin "2") (pinfunction "2_2") (pintype "passive"))
    )
    (net (code "96") (name "/NX5B_6") (class "Default")
      (node (ref "Q51") (pin "1") (pinfunction "B_1") (pintype "passive"))
      (node (ref "R59") (pin "2") (pinfunction "2_2") (pintype "passive"))
    )
    (net (code "97") (name "/NX5B_7") (class "Default")
      (node (ref "Q52") (pin "1") (pinfunction "B_1") (pintype "passive"))
      (node (ref "R60") (pin "2") (pinfunction "2_2") (pintype "passive"))
    )
    (net (code "98") (name "/NX5B_8") (class "Default")
      (node (ref "Q53") (pin "1") (pinfunction "B_1") (pintype "passive"))
      (node (ref "R61") (pin "2") (pinfunction "2_2") (pintype "passive"))
    )
    (net (code "99") (name "/NX5B_9") (class "Default")
      (node (ref "Q54") (pin "1") (pinfunction "B_1") (pintype "passive"))
      (node (ref "R62") (pin "2") (pinfunction "2_2") (pintype "passive"))
    )
    (net (code "100") (name "/NX5B_DP") (class "Default")
      (node (ref "Q55") (pin "1") (pinfunction "B_1") (pintype "passive"))
      (node (ref "R63") (pin "2") (pinfunction "2_2") (pintype "passive"))
    )
    (net (code "101") (name "/NX5_0") (class "Default")
      (node (ref "NX5") (pin "1") (pinfunction "0_1") (pintype "passive"))
      (node (ref "Q45") (pin "3") (pinfunction "C_3") (pintype "passive"))
    )
    (net (code "102") (name "/NX5_1") (class "Default")
      (node (ref "NX5") (pin "12") (pinfunction "+170_12") (pintype "passive"))
      (node (ref "Q46") (pin "3") (pinfunction "C_3") (pintype "passive"))
    )
    (net (code "103") (name "/NX5_2") (class "Default")
      (node (ref "NX5") (pin "3") (pinfunction "2_3") (pintype "passive"))
      (node (ref "Q47") (pin "3") (pinfunction "C_3") (pintype "passive"))
    )
    (net (code "104") (name "/NX5_3") (class "Default")
      (node (ref "NX5") (pin "4") (pinfunction "3_4") (pintype "passive"))
      (node (ref "Q48") (pin "3") (pinfunction "C_3") (pintype "passive"))
    )
    (net (code "105") (name "/NX5_4") (class "Default")
      (node (ref "NX5") (pin "5") (pinfunction "4_5") (pintype "passive"))
      (node (ref "Q49") (pin "3") (pinfunction "C_3") (pintype "passive"))
    )
    (net (code "106") (name "/NX5_5") (class "Default")
      (node (ref "NX5") (pin "6") (pinfunction "5_6") (pintype "passive"))
      (node (ref "Q50") (pin "3") (pinfunction "C_3") (pintype "passive"))
    )
    (net (code "107") (name "/NX5_6") (class "Default")
      (node (ref "NX5") (pin "7") (pinfunction "6_7") (pintype "passive"))
      (node (ref "Q51") (pin "3") (pinfunction "C_3") (pintype "passive"))
    )
    (net (code "108") (name "/NX5_7") (class "Default")
      (node (ref "NX5") (pin "8") (pinfunction "7_8") (pintype "passive"))
      (node (ref "Q52") (pin "3") (pinfunction "C_3") (pintype "passive"))
    )
    (net (code "109") (name "/NX5_8") (class "Default")
      (node (ref "NX5") (pin "9") (pinfunction "8_9") (pintype "passive"))
      (node (ref "Q53") (pin "3") (pinfunction "C_3") (pintype "passive"))
    )
    (net (code "110") (name "/NX5_9") (class "Default")
      (node (ref "NX5") (pin "10") (pinfunction "9_10") (pintype "passive"))
      (node (ref "Q54") (pin "3") (pinfunction "C_3") (pintype "passive"))
    )
    (net (code "111") (name "/NX5_DP") (class "Default")
      (node (ref "NX5") (pin "11") (pinfunction "DP_11") (pintype "passive"))
      (node (ref "Q55") (pin "3") (pinfunction "C_3") (pintype "passive"))
    )
    (net (code "112") (name "/NX6B_0") (class "Default")
      (node (ref "Q56") (pin "1") (pinfunction "B_1") (pintype "passive"))
      (node (ref "R64") (pin "2") (pinfunction "2_2") (pintype "passive"))
    )
    (net (code "113") (name "/NX6B_1") (class "Default")
      (node (ref "Q57") (pin "1") (pinfunction "B_1") (pintype "passive"))
      (node (ref "R65") (pin "2") (pinfunction "2_2") (pintype "passive"))
    )
    (net (code "114") (name "/NX6B_2") (class "Default")
      (node (ref "Q58") (pin "1") (pinfunction "B_1") (pintype "passive"))
      (node (ref "R66") (pin "2") (pinfunction "2_2") (pintype "passive"))
    )
    (net (code "115") (name "/NX6B_3") (class "Default")
      (node (ref "Q59") (pin "1") (pinfunction "B_1") (pintype "passive"))
      (node (ref "R67") (pin "2") (pinfunction "2_2") (pintype "passive"))
    )
    (net (code "116") (name "/NX6B_4") (class "Default")
      (node (ref "Q60") (pin "1") (pinfunction "B_1") (pintype "passive"))
      (node (ref "R68") (pin "2") (pinfunction "2_2") (pintype "passive"))
    )
    (net (code "117") (name "/NX6B_5") (class "Default")
      (node (ref "Q61") (pin "1") (pinfunction "B_1") (pintype "passive"))
      (node (ref "R69") (pin "2") (pinfunction "2_2") (pintype "passive"))
    )
    (net (code "118") (name "/NX6B_6") (class "Default")
      (node (ref "Q62") (pin "1") (pinfunction "B_1") (pintype "passive"))
      (node (ref "R70") (pin "2") (pinfunction "2_2") (pintype "passive"))
    )
    (net (code "119") (name "/NX6B_7") (class "Default")
      (node (ref "Q63") (pin "1") (pinfunction "B_1") (pintype "passive"))
      (node (ref "R71") (pin "2") (pinfunction "2_2") (pintype "passive"))
    )
    (net (code "120") (name "/NX6B_8") (class "Default")
      (node (ref "Q64") (pin "1") (pinfunction "B_1") (pintype "passive"))
      (node (ref "R72") (pin "2") (pinfunction "2_2") (pintype "passive"))
    )
    (net (code "121") (name "/NX6B_9") (class "Default")
      (node (ref "Q65") (pin "1") (pinfunction "B_1") (pintype "passive"))
      (node (ref "R73") (pin "2") (pinfunction "2_2") (pintype "passive"))
    )
    (net (code "122") (name "/NX6B_DP") (class "Default")
      (node (ref "Q66") (pin "1") (pinfunction "B_1") (pintype "passive"))
      (node (ref "R74") (pin "2") (pinfunction "2_2") (pintype "passive"))
    )
    (net (code "123") (name "/NX6_0") (class "Default")
      (node (ref "NX6") (pin "1") (pinfunction "0_1") (pintype "passive"))
      (node (ref "Q56") (pin "3") (pinfunction "C_3") (pintype "passive"))
    )
    (net (code "124") (name "/NX6_1") (class "Default")
      (node (ref "NX6") (pin "12") (pinfunction "+170_12") (pintype "passive"))
      (node (ref "Q57") (pin "3") (pinfunction "C_3") (pintype "passive"))
    )
    (net (code "125") (name "/NX6_2") (class "Default")
      (node (ref "NX6") (pin "3") (pinfunction "2_3") (pintype "passive"))
      (node (ref "Q58") (pin "3") (pinfunction "C_3") (pintype "passive"))
    )
    (net (code "126") (name "/NX6_3") (class "Default")
      (node (ref "NX6") (pin "4") (pinfunction "3_4") (pintype "passive"))
      (node (ref "Q59") (pin "3") (pinfunction "C_3") (pintype "passive"))
    )
    (net (code "127") (name "/NX6_4") (class "Default")
      (node (ref "NX6") (pin "5") (pinfunction "4_5") (pintype "passive"))
      (node (ref "Q60") (pin "3") (pinfunction "C_3") (pintype "passive"))
    )
    (net (code "128") (name "/NX6_5") (class "Default")
      (node (ref "NX6") (pin "6") (pinfunction "5_6") (pintype "passive"))
      (node (ref "Q61") (pin "3") (pinfunction "C_3") (pintype "passive"))
    )
    (net (code "129") (name "/NX6_6") (class "Default")
      (node (ref "NX6") (pin "7") (pinfunction "6_7") (pintype "passive"))
      (node (ref "Q62") (pin "3") (pinfunction "C_3") (pintype "passive"))
    )
    (net (code "130") (name "/NX6_7") (class "Default")
      (node (ref "NX6") (pin "8") (pinfunction "7_8") (pintype "passive"))
      (node (ref "Q63") (pin "3") (pinfunction "C_3") (pintype "passive"))
    )
    (net (code "131") (name "/NX6_8") (class "Default")
      (node (ref "NX6") (pin "9") (pinfunction "8_9") (pintype "passive"))
      (node (ref "Q64") (pin "3") (pinfunction "C_3") (pintype "passive"))
    )
    (net (code "132") (name "/NX6_9") (class "Default")
      (node (ref "NX6") (pin "10") (pinfunction "9_10") (pintype "passive"))
      (node (ref "Q65") (pin "3") (pinfunction "C_3") (pintype "passive"))
    )
    (net (code "133") (name "/NX6_DP") (class "Default")
      (node (ref "NX6") (pin "11") (pinfunction "DP_11") (pintype "passive"))
      (node (ref "Q66") (pin "3") (pinfunction "C_3") (pintype "passive"))
    )
    (net (code "134") (name "/NX7B_0") (class "Default")
      (node (ref "Q67") (pin "1") (pinfunction "B_1") (pintype "passive"))
      (node (ref "R75") (pin "2") (pinfunction "2_2") (pintype "passive"))
    )
    (net (code "135") (name "/NX7B_1") (class "Default")
      (node (ref "Q68") (pin "1") (pinfunction "B_1") (pintype "passive"))
      (node (ref "R76") (pin "2") (pinfunction "2_2") (pintype "passive"))
    )
    (net (code "136") (name "/NX7B_2") (class "Default")
      (node (ref "Q69") (pin "1") (pinfunction "B_1") (pintype "passive"))
      (node (ref "R77") (pin "2") (pinfunction "2_2") (pintype "passive"))
    )
    (net (code "137") (name "/NX7B_3") (class "Default")
      (node (ref "Q70") (pin "1") (pinfunction "B_1") (pintype "passive"))
      (node (ref "R78") (pin "2") (pinfunction "2_2") (pintype "passive"))
    )
    (net (code "138") (name "/NX7B_4") (class "Default")
      (node (ref "Q71") (pin "1") (pinfunction "B_1") (pintype "passive"))
      (node (ref "R79") (pin "2") (pinfunction "2_2") (pintype "passive"))
    )
    (net (code "139") (name "/NX7B_5") (class "Default")
      (node (ref "Q72") (pin "1") (pinfunction "B_1") (pintype "passive"))
      (node (ref "R80") (pin "2") (pinfunction "2_2") (pintype "passive"))
    )
    (net (code "140") (name "/NX7B_6") (class "Default")
      (node (ref "Q73") (pin "1") (pinfunction "B_1") (pintype "passive"))
      (node (ref "R81") (pin "2") (pinfunction "2_2") (pintype "passive"))
    )
    (net (code "141") (name "/NX7B_7") (class "Default")
      (node (ref "Q74") (pin "1") (pinfunction "B_1") (pintype "passive"))
      (node (ref "R82") (pin "2") (pinfunction "2_2") (pintype "passive"))
    )
    (net (code "142") (name "/NX7B_8") (class "Default")
      (node (ref "Q75") (pin "1") (pinfunction "B_1") (pintype "passive"))
      (node (ref "R83") (pin "2") (pinfunction "2_2") (pintype "passive"))
    )
    (net (code "143") (name "/NX7B_9") (class "Default")
      (node (ref "Q76") (pin "1") (pinfunction "B_1") (pintype "passive"))
      (node (ref "R84") (pin "2") (pinfunction "2_2") (pintype "passive"))
    )
    (net (code "144") (name "/NX7B_DP") (class "Default")
      (node (ref "Q77") (pin "1") (pinfunction "B_1") (pintype "passive"))
      (node (ref "R85") (pin "2") (pinfunction "2_2") (pintype "passive"))
    )
    (net (code "145") (name "/NX7_0") (class "Default")
      (node (ref "NX7") (pin "1") (pinfunction "0_1") (pintype "passive"))
      (node (ref "Q67") (pin "3") (pinfunction "C_3") (pintype "passive"))
    )
    (net (code "146") (name "/NX7_1") (class "Default")
      (node (ref "NX7") (pin "12") (pinfunction "+170_12") (pintype "passive"))
      (node (ref "Q68") (pin "3") (pinfunction "C_3") (pintype "passive"))
    )
    (net (code "147") (name "/NX7_2") (class "Default")
      (node (ref "NX7") (pin "3") (pinfunction "2_3") (pintype "passive"))
      (node (ref "Q69") (pin "3") (pinfunction "C_3") (pintype "passive"))
    )
    (net (code "148") (name "/NX7_3") (class "Default")
      (node (ref "NX7") (pin "4") (pinfunction "3_4") (pintype "passive"))
      (node (ref "Q70") (pin "3") (pinfunction "C_3") (pintype "passive"))
    )
    (net (code "149") (name "/NX7_4") (class "Default")
      (node (ref "NX7") (pin "5") (pinfunction "4_5") (pintype "passive"))
      (node (ref "Q71") (pin "3") (pinfunction "C_3") (pintype "passive"))
    )
    (net (code "150") (name "/NX7_5") (class "Default")
      (node (ref "NX7") (pin "6") (pinfunction "5_6") (pintype "passive"))
      (node (ref "Q72") (pin "3") (pinfunction "C_3") (pintype "passive"))
    )
    (net (code "151") (name "/NX7_6") (class "Default")
      (node (ref "NX7") (pin "7") (pinfunction "6_7") (pintype "passive"))
      (node (ref "Q73") (pin "3") (pinfunction "C_3") (pintype "passive"))
    )
    (net (code "152") (name "/NX7_7") (class "Default")
      (node (ref "NX7") (pin "8") (pinfunction "7_8") (pintype "passive"))
      (node (ref "Q74") (pin "3") (pinfunction "C_3") (pintype "passive"))
    )
    (net (code "153") (name "/NX7_8") (class "Default")
      (node (ref "NX7") (pin "9") (pinfunction "8_9") (pintype "passive"))
      (node (ref "Q75") (pin "3") (pinfunction "C_3") (pintype "passive"))
    )
    (net (code "154") (name "/NX7_9") (class "Default")
      (node (ref "NX7") (pin "10") (pinfunction "9_10") (pintype "passive"))
      (node (ref "Q76") (pin "3") (pinfunction "C_3") (pintype "passive"))
    )
    (net (code "155") (name "/NX7_DP") (class "Default")
      (node (ref "NX7") (pin "11") (pinfunction "DP_11") (pintype "passive"))
      (node (ref "Q77") (pin "3") (pinfunction "C_3") (pintype "passive"))
    )
    (net (code "156") (name "/NX8B_0") (class "Default")
      (node (ref "Q78") (pin "1") (pinfunction "B_1") (pintype "passive"))
      (node (ref "R86") (pin "2") (pinfunction "2_2") (pintype "passive"))
    )
    (net (code "157") (name "/NX8B_1") (class "Default")
      (node (ref "Q79") (pin "1") (pinfunction "B_1") (pintype "passive"))
      (node (ref "R87") (pin "2") (pinfunction "2_2") (pintype "passive"))
    )
    (net (code "158") (name "/NX8B_2") (class "Default")
      (node (ref "Q80") (pin "1") (pinfunction "B_1") (pintype "passive"))
      (node (ref "R88") (pin "2") (pinfunction "2_2") (pintype "passive"))
    )
    (net (code "159") (name "/NX8B_3") (class "Default")
      (node (ref "Q81") (pin "1") (pinfunction "B_1") (pintype "passive"))
      (node (ref "R89") (pin "2") (pinfunction "2_2") (pintype "passive"))
    )
    (net (code "160") (name "/NX8B_4") (class "Default")
      (node (ref "Q82") (pin "1") (pinfunction "B_1") (pintype "passive"))
      (node (ref "R90") (pin "2") (pinfunction "2_2") (pintype "passive"))
    )
    (net (code "161") (name "/NX8B_5") (class "Default")
      (node (ref "Q83") (pin "1") (pinfunction "B_1") (pintype "passive"))
      (node (ref "R91") (pin "2") (pinfunction "2_2") (pintype "passive"))
    )
    (net (code "162") (name "/NX8B_6") (class "Default")
      (node (ref "Q84") (pin "1") (pinfunction "B_1") (pintype "passive"))
      (node (ref "R92") (pin "2") (pinfunction "2_2") (pintype "passive"))
    )
    (net (code "163") (name "/NX8B_7") (class "Default")
      (node (ref "Q85") (pin "1") (pinfunction "B_1") (pintype "passive"))
      (node (ref "R93") (pin "2") (pinfunction "2_2") (pintype "passive"))
    )
    (net (code "164") (name "/NX8B_8") (class "Default")
      (node (ref "Q86") (pin "1") (pinfunction "B_1") (pintype "passive"))
      (node (ref "R94") (pin "2") (pinfunction "2_2") (pintype "passive"))
    )
    (net (code "165") (name "/NX8B_9") (class "Default")
      (node (ref "Q87") (pin "1") (pinfunction "B_1") (pintype "passive"))
      (node (ref "R95") (pin "2") (pinfunction "2_2") (pintype "passive"))
    )
    (net (code "166") (name "/NX8B_DP") (class "Default")
      (node (ref "Q88") (pin "1") (pinfunction "B_1") (pintype "passive"))
      (node (ref "R96") (pin "2") (pinfunction "2_2") (pintype "passive"))
    )
    (net (code "167") (name "/NX8_0") (class "Default")
      (node (ref "NX8") (pin "1") (pinfunction "0_1") (pintype "passive"))
      (node (ref "Q78") (pin "3") (pinfunction "C_3") (pintype "passive"))
    )
    (net (code "168") (name "/NX8_1") (class "Default")
      (node (ref "NX8") (pin "12") (pinfunction "+170_12") (pintype "passive"))
      (node (ref "Q79") (pin "3") (pinfunction "C_3") (pintype "passive"))
    )
    (net (code "169") (name "/NX8_2") (class "Default")
      (node (ref "NX8") (pin "3") (pinfunction "2_3") (pintype "passive"))
      (node (ref "Q80") (pin "3") (pinfunction "C_3") (pintype "passive"))
    )
    (net (code "170") (name "/NX8_3") (class "Default")
      (node (ref "NX8") (pin "4") (pinfunction "3_4") (pintype "passive"))
      (node (ref "Q81") (pin "3") (pinfunction "C_3") (pintype "passive"))
    )
    (net (code "171") (name "/NX8_4") (class "Default")
      (node (ref "NX8") (pin "5") (pinfunction "4_5") (pintype "passive"))
      (node (ref "Q82") (pin "3") (pinfunction "C_3") (pintype "passive"))
    )
    (net (code "172") (name "/NX8_5") (class "Default")
      (node (ref "NX8") (pin "6") (pinfunction "5_6") (pintype "passive"))
      (node (ref "Q83") (pin "3") (pinfunction "C_3") (pintype "passive"))
    )
    (net (code "173") (name "/NX8_6") (class "Default")
      (node (ref "NX8") (pin "7") (pinfunction "6_7") (pintype "passive"))
      (node (ref "Q84") (pin "3") (pinfunction "C_3") (pintype "passive"))
    )
    (net (code "174") (name "/NX8_7") (class "Default")
      (node (ref "NX8") (pin "8") (pinfunction "7_8") (pintype "passive"))
      (node (ref "Q85") (pin "3") (pinfunction "C_3") (pintype "passive"))
    )
    (net (code "175") (name "/NX8_8") (class "Default")
      (node (ref "NX8") (pin "9") (pinfunction "8_9") (pintype "passive"))
      (node (ref "Q86") (pin "3") (pinfunction "C_3") (pintype "passive"))
    )
    (net (code "176") (name "/NX8_9") (class "Default")
      (node (ref "NX8") (pin "10") (pinfunction "9_10") (pintype "passive"))
      (node (ref "Q87") (pin "3") (pinfunction "C_3") (pintype "passive"))
    )
    (net (code "177") (name "/NX8_DP") (class "Default")
      (node (ref "NX8") (pin "11") (pinfunction "DP_11") (pintype "passive"))
      (node (ref "Q88") (pin "3") (pinfunction "C_3") (pintype "passive"))
    )
    (net (code "178") (name "/Q1") (class "Default")
      (node (ref "R9") (pin "1") (pinfunction "1_1") (pintype "passive"))
    )
    (net (code "179") (name "/Q2") (class "Default")
      (node (ref "R10") (pin "1") (pinfunction "1_1") (pintype "passive"))
    )
    (net (code "180") (name "/Q3") (class "Default")
      (node (ref "R11") (pin "1") (pinfunction "1_1") (pintype "passive"))
    )
    (net (code "181") (name "/Q4") (class "Default")
      (node (ref "R12") (pin "1") (pinfunction "1_1") (pintype "passive"))
    )
    (net (code "182") (name "/Q5") (class "Default")
      (node (ref "R13") (pin "1") (pinfunction "1_1") (pintype "passive"))
    )
    (net (code "183") (name "/Q6") (class "Default")
      (node (ref "R14") (pin "1") (pinfunction "1_1") (pintype "passive"))
    )
    (net (code "184") (name "/Q7") (class "Default")
      (node (ref "R15") (pin "1") (pinfunction "1_1") (pintype "passive"))
    )
    (net (code "185") (name "/Q8") (class "Default")
      (node (ref "R16") (pin "1") (pinfunction "1_1") (pintype "passive"))
    )
    (net (code "186") (name "/Q9") (class "Default")
      (node (ref "R17") (pin "1") (pinfunction "1_1") (pintype "passive"))
    )
    (net (code "187") (name "/Q10") (class "Default")
      (node (ref "R18") (pin "1") (pinfunction "1_1") (pintype "passive"))
    )
    (net (code "188") (name "/Q11") (class "Default")
      (node (ref "R19") (pin "1") (pinfunction "1_1") (pintype "passive"))
    )
    (net (code "189") (name "/Q12") (class "Default")
      (node (ref "R20") (pin "1") (pinfunction "1_1") (pintype "passive"))
    )
    (net (code "190") (name "/Q13") (class "Default")
      (node (ref "R21") (pin "1") (pinfunction "1_1") (pintype "passive"))
    )
    (net (code "191") (name "/Q14") (class "Default")
      (node (ref "R22") (pin "1") (pinfunction "1_1") (pintype "passive"))
    )
    (net (code "192") (name "/Q15") (class "Default")
      (node (ref "R23") (pin "1") (pinfunction "1_1") (pintype "passive"))
    )
    (net (code "193") (name "/Q16") (class "Default")
      (node (ref "R24") (pin "1") (pinfunction "1_1") (pintype "passive"))
    )
    (net (code "194") (name "/Q17") (class "Default")
      (node (ref "R25") (pin "1") (pinfunction "1_1") (pintype "passive"))
    )
    (net (code "195") (name "/Q18") (class "Default")
      (node (ref "R26") (pin "1") (pinfunction "1_1") (pintype "passive"))
    )
    (net (code "196") (name "/Q19") (class "Default")
      (node (ref "R27") (pin "1") (pinfunction "1_1") (pintype "passive"))
    )
    (net (code "197") (name "/Q20") (class "Default")
      (node (ref "R28") (pin "1") (pinfunction "1_1") (pintype "passive"))
    )
    (net (code "198") (name "/Q21") (class "Default")
      (node (ref "R29") (pin "1") (pinfunction "1_1") (pintype "passive"))
    )
    (net (code "199") (name "/Q22") (class "Default")
      (node (ref "R30") (pin "1") (pinfunction "1_1") (pintype "passive"))
    )
    (net (code "200") (name "/Q23") (class "Default")
      (node (ref "R31") (pin "1") (pinfunction "1_1") (pintype "passive"))
    )
    (net (code "201") (name "/Q24") (class "Default")
      (node (ref "R32") (pin "1") (pinfunction "1_1") (pintype "passive"))
    )
    (net (code "202") (name "/Q25") (class "Default")
      (node (ref "R33") (pin "1") (pinfunction "1_1") (pintype "passive"))
    )
    (net (code "203") (name "/Q26") (class "Default")
      (node (ref "R34") (pin "1") (pinfunction "1_1") (pintype "passive"))
    )
    (net (code "204") (name "/Q27") (class "Default")
      (node (ref "R35") (pin "1") (pinfunction "1_1") (pintype "passive"))
    )
    (net (code "205") (name "/Q28") (class "Default")
      (node (ref "R36") (pin "1") (pinfunction "1_1") (pintype "passive"))
    )
    (net (code "206") (name "/Q29") (class "Default")
      (node (ref "R37") (pin "1") (pinfunction "1_1") (pintype "passive"))
    )
    (net (code "207") (name "/Q30") (class "Default")
      (node (ref "R38") (pin "1") (pinfunction "1_1") (pintype "passive"))
    )
    (net (code "208") (name "/Q31") (class "Default")
      (node (ref "R39") (pin "1") (pinfunction "1_1") (pintype "passive"))
    )
    (net (code "209") (name "/Q32") (class "Default")
      (node (ref "R40") (pin "1") (pinfunction "1_1") (pintype "passive"))
    )
    (net (code "210") (name "/Q33") (class "Default")
      (node (ref "R41") (pin "1") (pinfunction "1_1") (pintype "passive"))
    )
    (net (code "211") (name "/Q34") (class "Default")
      (node (ref "R42") (pin "1") (pinfunction "1_1") (pintype "passive"))
    )
    (net (code "212") (name "/Q35") (class "Default")
      (node (ref "R43") (pin "1") (pinfunction "1_1") (pintype "passive"))
    )
    (net (code "213") (name "/Q36") (class "Default")
      (node (ref "R44") (pin "1") (pinfunction "1_1") (pintype "passive"))
    )
    (net (code "214") (name "/Q37") (class "Default")
      (node (ref "R45") (pin "1") (pinfunction "1_1") (pintype "passive"))
    )
    (net (code "215") (name "/Q38") (class "Default")
      (node (ref "R46") (pin "1") (pinfunction "1_1") (pintype "passive"))
    )
    (net (code "216") (name "/Q39") (class "Default")
      (node (ref "R47") (pin "1") (pinfunction "1_1") (pintype "passive"))
    )
    (net (code "217") (name "/Q40") (class "Default")
      (node (ref "R48") (pin "1") (pinfunction "1_1") (pintype "passive"))
    )
    (net (code "218") (name "/Q41") (class "Default")
      (node (ref "R49") (pin "1") (pinfunction "1_1") (pintype "passive"))
    )
    (net (code "219") (name "/Q42") (class "Default")
      (node (ref "R50") (pin "1") (pinfunction "1_1") (pintype "passive"))
    )
    (net (code "220") (name "/Q43") (class "Default")
      (node (ref "R51") (pin "1") (pinfunction "1_1") (pintype "passive"))
    )
    (net (code "221") (name "/Q44") (class "Default")
      (node (ref "R52") (pin "1") (pinfunction "1_1") (pintype "passive"))
    )
    (net (code "222") (name "/Q45") (class "Default")
      (node (ref "R53") (pin "1") (pinfunction "1_1") (pintype "passive"))
    )
    (net (code "223") (name "/Q46") (class "Default")
      (node (ref "R54") (pin "1") (pinfunction "1_1") (pintype "passive"))
    )
    (net (code "224") (name "/Q47") (class "Default")
      (node (ref "R55") (pin "1") (pinfunction "1_1") (pintype "passive"))
    )
    (net (code "225") (name "/Q48") (class "Default")
      (node (ref "R56") (pin "1") (pinfunction "1_1") (pintype "passive"))
    )
    (net (code "226") (name "/Q49") (class "Default")
      (node (ref "R57") (pin "1") (pinfunction "1_1") (pintype "passive"))
    )
    (net (code "227") (name "/Q50") (class "Default")
      (node (ref "R58") (pin "1") (pinfunction "1_1") (pintype "passive"))
    )
    (net (code "228") (name "/Q51") (class "Default")
      (node (ref "R59") (pin "1") (pinfunction "1_1") (pintype "passive"))
    )
    (net (code "229") (name "/Q52") (class "Default")
      (node (ref "R60") (pin "1") (pinfunction "1_1") (pintype "passive"))
    )
    (net (code "230") (name "/Q53") (class "Default")
      (node (ref "R61") (pin "1") (pinfunction "1_1") (pintype "passive"))
    )
    (net (code "231") (name "/Q54") (class "Default")
      (node (ref "R62") (pin "1") (pinfunction "1_1") (pintype "passive"))
    )
    (net (code "232") (name "/Q55") (class "Default")
      (node (ref "R63") (pin "1") (pinfunction "1_1") (pintype "passive"))
    )
    (net (code "233") (name "/Q56") (class "Default")
      (node (ref "R64") (pin "1") (pinfunction "1_1") (pintype "passive"))
    )
    (net (code "234") (name "/Q57") (class "Default")
      (node (ref "R65") (pin "1") (pinfunction "1_1") (pintype "passive"))
    )
    (net (code "235") (name "/Q58") (class "Default")
      (node (ref "R66") (pin "1") (pinfunction "1_1") (pintype "passive"))
    )
    (net (code "236") (name "/Q59") (class "Default")
      (node (ref "R67") (pin "1") (pinfunction "1_1") (pintype "passive"))
    )
    (net (code "237") (name "/Q60") (class "Default")
      (node (ref "R68") (pin "1") (pinfunction "1_1") (pintype "passive"))
    )
    (net (code "238") (name "/Q61") (class "Default")
      (node (ref "R69") (pin "1") (pinfunction "1_1") (pintype "passive"))
    )
    (net (code "239") (name "/Q62") (class "Default")
      (node (ref "R70") (pin "1") (pinfunction "1_1") (pintype "passive"))
    )
    (net (code "240") (name "/Q63") (class "Default")
      (node (ref "R71") (pin "1") (pinfunction "1_1") (pintype "passive"))
    )
    (net (code "241") (name "/Q64") (class "Default")
      (node (ref "R72") (pin "1") (pinfunction "1_1") (pintype "passive"))
    )
    (net (code "242") (name "/Q65") (class "Default")
      (node (ref "R73") (pin "1") (pinfunction "1_1") (pintype "passive"))
    )
    (net (code "243") (name "/Q66") (class "Default")
      (node (ref "R74") (pin "1") (pinfunction "1_1") (pintype "passive"))
    )
    (net (code "244") (name "/Q67") (class "Default")
      (node (ref "R75") (pin "1") (pinfunction "1_1") (pintype "passive"))
    )
    (net (code "245") (name "/Q68") (class "Default")
      (node (ref "R76") (pin "1") (pinfunction "1_1") (pintype "passive"))
    )
    (net (code "246") (name "/Q69") (class "Default")
      (node (ref "R77") (pin "1") (pinfunction "1_1") (pintype "passive"))
    )
    (net (code "247") (name "/Q70") (class "Default")
      (node (ref "R78") (pin "1") (pinfunction "1_1") (pintype "passive"))
    )
    (net (code "248") (name "/Q71") (class "Default")
      (node (ref "R79") (pin "1") (pinfunction "1_1") (pintype "passive"))
    )
    (net (code "249") (name "/Q72") (class "Default")
      (node (ref "R80") (pin "1") (pinfunction "1_1") (pintype "passive"))
    )
    (net (code "250") (name "/Q73") (class "Default")
      (node (ref "R81") (pin "1") (pinfunction "1_1") (pintype "passive"))
    )
    (net (code "251") (name "/Q74") (class "Default")
      (node (ref "R82") (pin "1") (pinfunction "1_1") (pintype "passive"))
    )
    (net (code "252") (name "/Q75") (class "Default")
      (node (ref "R83") (pin "1") (pinfunction "1_1") (pintype "passive"))
    )
    (net (code "253") (name "/Q76") (class "Default")
      (node (ref "R84") (pin "1") (pinfunction "1_1") (pintype "passive"))
    )
    (net (code "254") (name "/Q77") (class "Default")
      (node (ref "R85") (pin "1") (pinfunction "1_1") (pintype "passive"))
    )
    (net (code "255") (name "/Q78") (class "Default")
      (node (ref "R86") (pin "1") (pinfunction "1_1") (pintype "passive"))
    )
    (net (code "256") (name "/Q79") (class "Default")
      (node (ref "R87") (pin "1") (pinfunction "1_1") (pintype "passive"))
    )
    (net (code "257") (name "/Q80") (class "Default")
      (node (ref "R88") (pin "1") (pinfunction "1_1") (pintype "passive"))
    )
    (net (code "258") (name "/Q81") (class "Default")
      (node (ref "R89") (pin "1") (pinfunction "1_1") (pintype "passive"))
    )
    (net (code "259") (name "/Q82") (class "Default")
      (node (ref "R90") (pin "1") (pinfunction "1_1") (pintype "passive"))
    )
    (net (code "260") (name "/Q83") (class "Default")
      (node (ref "R91") (pin "1") (pinfunction "1_1") (pintype "passive"))
    )
    (net (code "261") (name "/Q84") (class "Default")
      (node (ref "R92") (pin "1") (pinfunction "1_1") (pintype "passive"))
    )
    (net (code "262") (name "/Q85") (class "Default")
      (node (ref "R93") (pin "1") (pinfunction "1_1") (pintype "passive"))
    )
    (net (code "263") (name "/Q86") (class "Default")
      (node (ref "R94") (pin "1") (pinfunction "1_1") (pintype "passive"))
    )
    (net (code "264") (name "/Q87") (class "Default")
      (node (ref "R95") (pin "1") (pinfunction "1_1") (pintype "passive"))
    )
    (net (code "265") (name "/Q88") (class "Default")
      (node (ref "R96") (pin "1") (pinfunction "1_1") (pintype "passive"))
    )
    (net (code "266") (name "GND") (class "Default")
      (node (ref "Q1") (pin "2") (pinfunction "E_2") (pintype "passive"))
      (node (ref "Q10") (pin "2") (pinfunction "E_2") (pintype "passive"))
      (node (ref "Q11") (pin "2") (pinfunction "E_2") (pintype "passive"))
      (node (ref "Q12") (pin "2") (pinfunction "E_2") (pintype "passive"))
      (node (ref "Q13") (pin "2") (pinfunction "E_2") (pintype "passive"))
      (node (ref "Q14") (pin "2") (pinfunction "E_2") (pintype "passive"))
      (node (ref "Q15") (pin "2") (pinfunction "E_2") (pintype "passive"))
      (node (ref "Q16") (pin "2") (pinfunction "E_2") (pintype "passive"))
      (node (ref "Q17") (pin "2") (pinfunction "E_2") (pintype "passive"))
      (node (ref "Q18") (pin "2") (pinfunction "E_2") (pintype "passive"))
      (node (ref "Q19") (pin "2") (pinfunction "E_2") (pintype "passive"))
      (node (ref "Q2") (pin "2") (pinfunction "E_2") (pintype "passive"))
      (node (ref "Q20") (pin "2") (pinfunction "E_2") (pintype "passive"))
      (node (ref "Q21") (pin "2") (pinfunction "E_2") (pintype "passive"))
      (node (ref "Q22") (pin "2") (pinfunction "E_2") (pintype "passive"))
      (node (ref "Q23") (pin "2") (pinfunction "E_2") (pintype "passive"))
      (node (ref "Q24") (pin "2") (pinfunction "E_2") (pintype "passive"))
      (node (ref "Q25") (pin "2") (pinfunction "E_2") (pintype "passive"))
      (node (ref "Q26") (pin "2") (pinfunction "E_2") (pintype "passive"))
      (node (ref "Q27") (pin "2") (pinfunction "E_2") (pintype "passive"))
      (node (ref "Q28") (pin "2") (pinfunction "E_2") (pintype "passive"))
      (node (ref "Q29") (pin "2") (pinfunction "E_2") (pintype "passive"))
      (node (ref "Q3") (pin "2") (pinfunction "E_2") (pintype "passive"))
      (node (ref "Q30") (pin "2") (pinfunction "E_2") (pintype "passive"))
      (node (ref "Q31") (pin "2") (pinfunction "E_2") (pintype "passive"))
      (node (ref "Q32") (pin "2") (pinfunction "E_2") (pintype "passive"))
      (node (ref "Q33") (pin "2") (pinfunction "E_2") (pintype "passive"))
      (node (ref "Q34") (pin "2") (pinfunction "E_2") (pintype "passive"))
      (node (ref "Q35") (pin "2") (pinfunction "E_2") (pintype "passive"))
      (node (ref "Q36") (pin "2") (pinfunction "E_2") (pintype "passive"))
      (node (ref "Q37") (pin "2") (pinfunction "E_2") (pintype "passive"))
      (node (ref "Q38") (pin "2") (pinfunction "E_2") (pintype "passive"))
      (node (ref "Q39") (pin "2") (pinfunction "E_2") (pintype "passive"))
      (node (ref "Q4") (pin "2") (pinfunction "E_2") (pintype "passive"))
      (node (ref "Q40") (pin "2") (pinfunction "E_2") (pintype "passive"))
      (node (ref "Q41") (pin "2") (pinfunction "E_2") (pintype "passive"))
      (node (ref "Q42") (pin "2") (pinfunction "E_2") (pintype "passive"))
      (node (ref "Q43") (pin "2") (pinfunction "E_2") (pintype "passive"))
      (node (ref "Q44") (pin "2") (pinfunction "E_2") (pintype "passive"))
      (node (ref "Q45") (pin "2") (pinfunction "E_2") (pintype "passive"))
      (node (ref "Q46") (pin "2") (pinfunction "E_2") (pintype "passive"))
      (node (ref "Q47") (pin "2") (pinfunction "E_2") (pintype "passive"))
      (node (ref "Q48") (pin "2") (pinfunction "E_2") (pintype "passive"))
      (node (ref "Q49") (pin "2") (pinfunction "E_2") (pintype "passive"))
      (node (ref "Q5") (pin "2") (pinfunction "E_2") (pintype "passive"))
      (node (ref "Q50") (pin "2") (pinfunction "E_2") (pintype "passive"))
      (node (ref "Q51") (pin "2") (pinfunction "E_2") (pintype "passive"))
      (node (ref "Q52") (pin "2") (pinfunction "E_2") (pintype "passive"))
      (node (ref "Q53") (pin "2") (pinfunction "E_2") (pintype "passive"))
      (node (ref "Q54") (pin "2") (pinfunction "E_2") (pintype "passive"))
      (node (ref "Q55") (pin "2") (pinfunction "E_2") (pintype "passive"))
      (node (ref "Q56") (pin "2") (pinfunction "E_2") (pintype "passive"))
      (node (ref "Q57") (pin "2") (pinfunction "E_2") (pintype "passive"))
      (node (ref "Q58") (pin "2") (pinfunction "E_2") (pintype "passive"))
      (node (ref "Q59") (pin "2") (pinfunction "E_2") (pintype "passive"))
      (node (ref "Q6") (pin "2") (pinfunction "E_2") (pintype "passive"))
      (node (ref "Q60") (pin "2") (pinfunction "E_2") (pintype "passive"))
      (node (ref "Q61") (pin "2") (pinfunction "E_2") (pintype "passive"))
      (node (ref "Q62") (pin "2") (pinfunction "E_2") (pintype "passive"))
      (node (ref "Q63") (pin "2") (pinfunction "E_2") (pintype "passive"))
      (node (ref "Q64") (pin "2") (pinfunction "E_2") (pintype "passive"))
      (node (ref "Q65") (pin "2") (pinfunction "E_2") (pintype "passive"))
      (node (ref "Q66") (pin "2") (pinfunction "E_2") (pintype "passive"))
      (node (ref "Q67") (pin "2") (pinfunction "E_2") (pintype "passive"))
      (node (ref "Q68") (pin "2") (pinfunction "E_2") (pintype "passive"))
      (node (ref "Q69") (pin "2") (pinfunction "E_2") (pintype "passive"))
      (node (ref "Q7") (pin "2") (pinfunction "E_2") (pintype "passive"))
      (node (ref "Q70") (pin "2") (pinfunction "E_2") (pintype "passive"))
      (node (ref "Q71") (pin "2") (pinfunction "E_2") (pintype "passive"))
      (node (ref "Q72") (pin "2") (pinfunction "E_2") (pintype "passive"))
      (node (ref "Q73") (pin "2") (pinfunction "E_2") (pintype "passive"))
      (node (ref "Q74") (pin "2") (pinfunction "E_2") (pintype "passive"))
      (node (ref "Q75") (pin "2") (pinfunction "E_2") (pintype "passive"))
      (node (ref "Q76") (pin "2") (pinfunction "E_2") (pintype "passive"))
      (node (ref "Q77") (pin "2") (pinfunction "E_2") (pintype "passive"))
      (node (ref "Q78") (pin "2") (pinfunction "E_2") (pintype "passive"))
      (node (ref "Q79") (pin "2") (pinfunction "E_2") (pintype "passive"))
      (node (ref "Q8") (pin "2") (pinfunction "E_2") (pintype "passive"))
      (node (ref "Q80") (pin "2") (pinfunction "E_2") (pintype "passive"))
      (node (ref "Q81") (pin "2") (pinfunction "E_2") (pintype "passive"))
      (node (ref "Q82") (pin "2") (pinfunction "E_2") (pintype "passive"))
      (node (ref "Q83") (pin "2") (pinfunction "E_2") (pintype "passive"))
      (node (ref "Q84") (pin "2") (pinfunction "E_2") (pintype "passive"))
      (node (ref "Q85") (pin "2") (pinfunction "E_2") (pintype "passive"))
      (node (ref "Q86") (pin "2") (pinfunction "E_2") (pintype "passive"))
      (node (ref "Q87") (pin "2") (pinfunction "E_2") (pintype "passive"))
      (node (ref "Q88") (pin "2") (pinfunction "E_2") (pintype "passive"))
      (node (ref "Q9") (pin "2") (pinfunction "E_2") (pintype "passive"))
    )
    (net (code "267") (name "Net-(NX1-1)") (class "Default")
      (node (ref "NX1") (pin "2") (pinfunction "1_2") (pintype "passive"))
      (node (ref "R1") (pin "1") (pinfunction "1_1") (pintype "passive"))
    )
    (net (code "268") (name "Net-(NX2-1)") (class "Default")
      (node (ref "NX2") (pin "2") (pinfunction "1_2") (pintype "passive"))
      (node (ref "R2") (pin "1") (pinfunction "1_1") (pintype "passive"))
    )
    (net (code "269") (name "Net-(NX3-1)") (class "Default")
      (node (ref "NX3") (pin "2") (pinfunction "1_2") (pintype "passive"))
      (node (ref "R3") (pin "1") (pinfunction "1_1") (pintype "passive"))
    )
    (net (code "270") (name "Net-(NX4-1)") (class "Default")
      (node (ref "NX4") (pin "2") (pinfunction "1_2") (pintype "passive"))
      (node (ref "R4") (pin "1") (pinfunction "1_1") (pintype "passive"))
    )
    (net (code "271") (name "Net-(NX5-1)") (class "Default")
      (node (ref "NX5") (pin "2") (pinfunction "1_2") (pintype "passive"))
      (node (ref "R5") (pin "1") (pinfunction "1_1") (pintype "passive"))
    )
    (net (code "272") (name "Net-(NX6-1)") (class "Default")
      (node (ref "NX6") (pin "2") (pinfunction "1_2") (pintype "passive"))
      (node (ref "R6") (pin "1") (pinfunction "1_1") (pintype "passive"))
    )
    (net (code "273") (name "Net-(NX7-1)") (class "Default")
      (node (ref "NX7") (pin "2") (pinfunction "1_2") (pintype "passive"))
      (node (ref "R7") (pin "1") (pinfunction "1_1") (pintype "passive"))
    )
    (net (code "274") (name "Net-(NX8-1)") (class "Default")
      (node (ref "NX8") (pin "2") (pinfunction "1_2") (pintype "passive"))
      (node (ref "R8") (pin "1") (pinfunction "1_1") (pintype "passive"))
    )
  )
)
